# GTM900-breakout.net
KiCad netlist of a schematic drawn in EAGLE
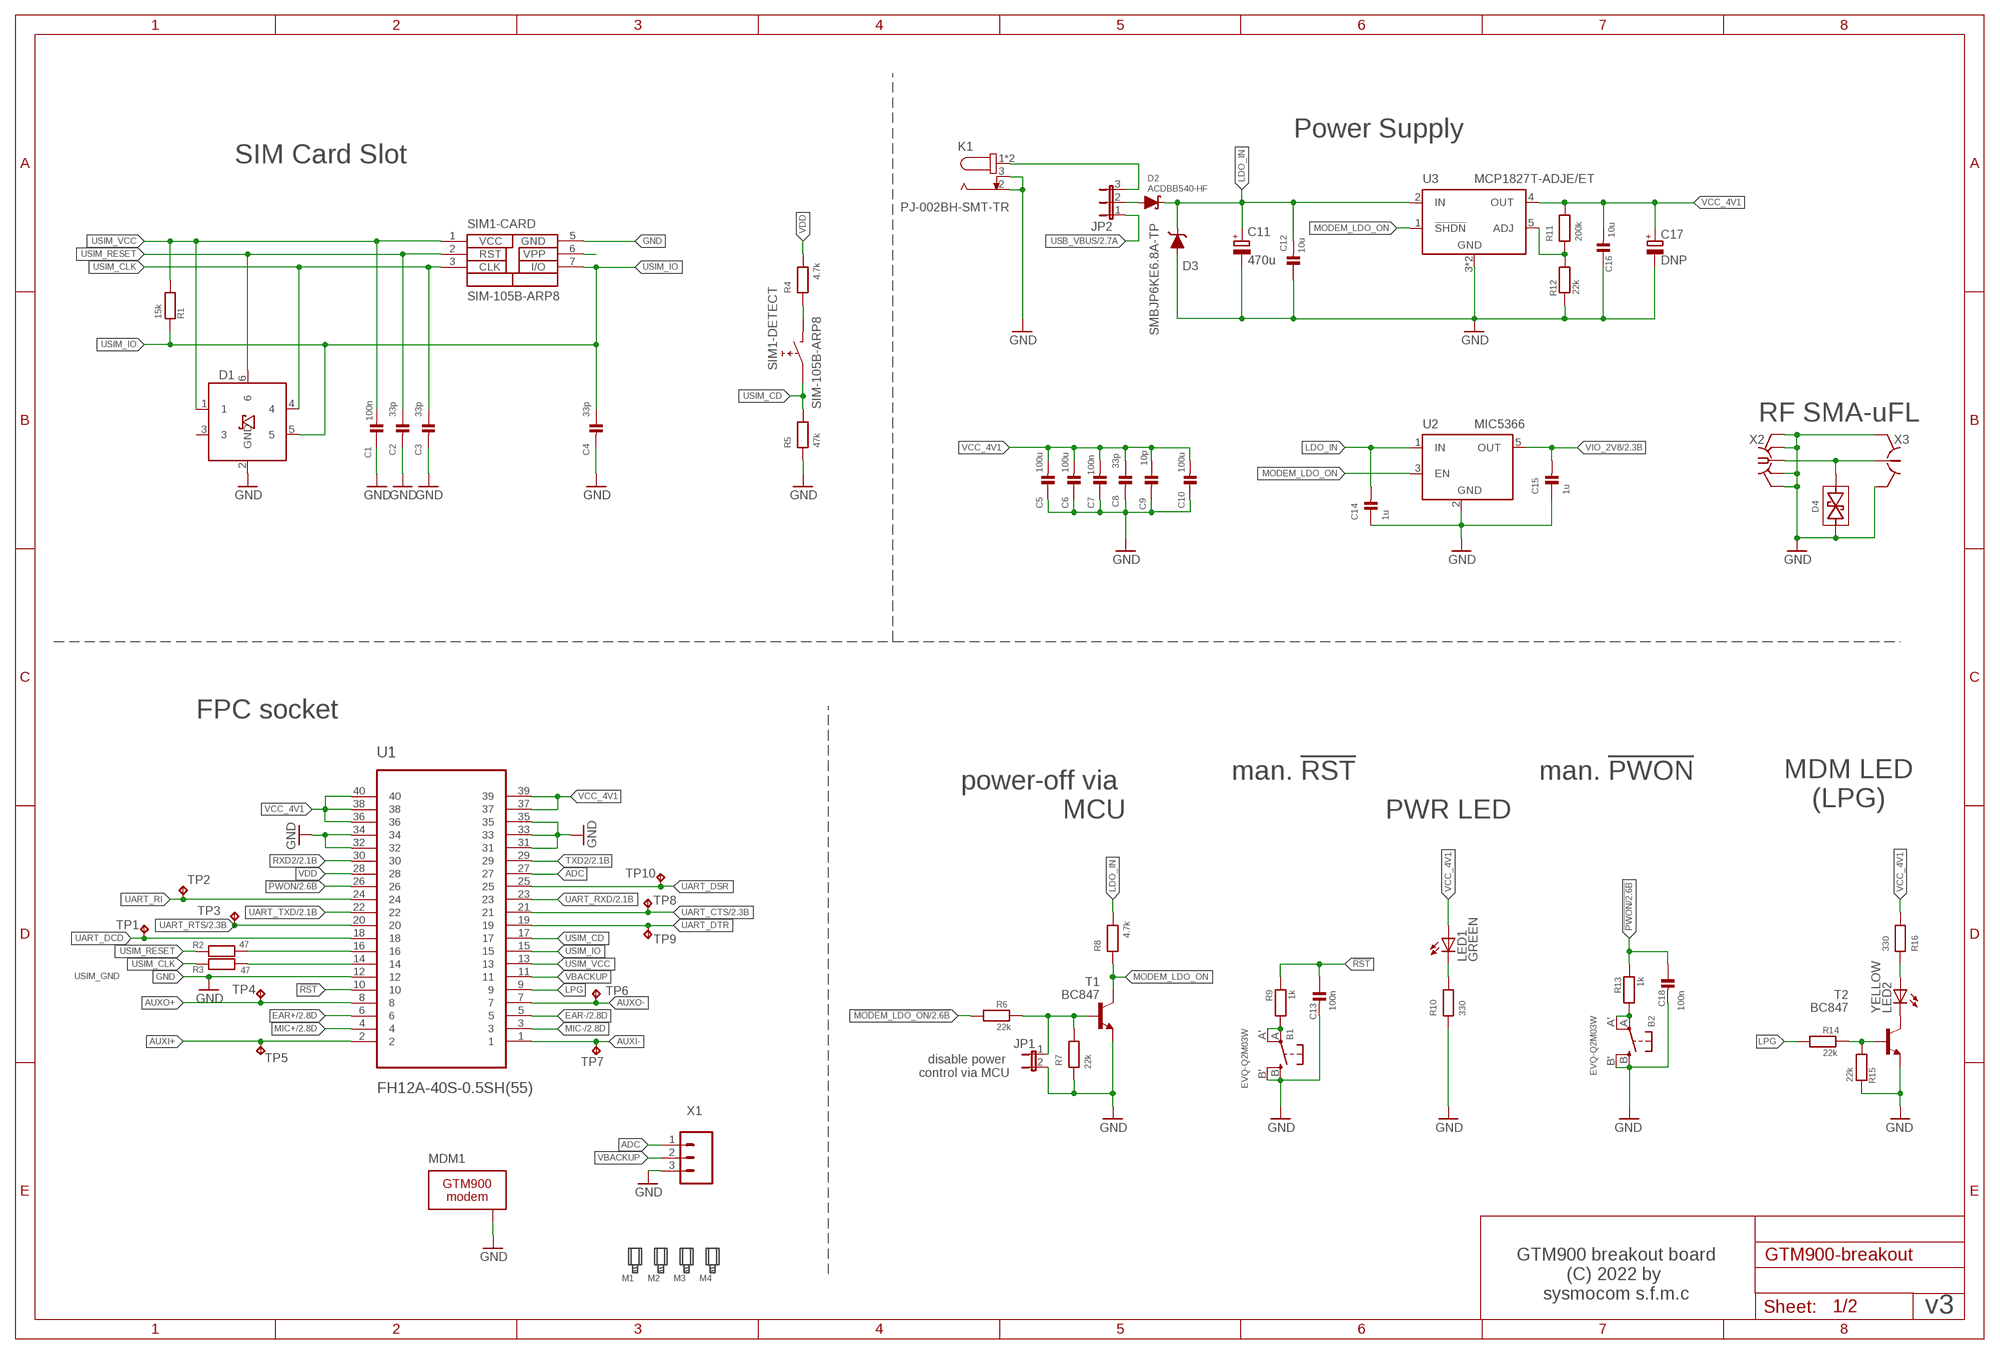
[diagram p0: schematic, sheet 1]
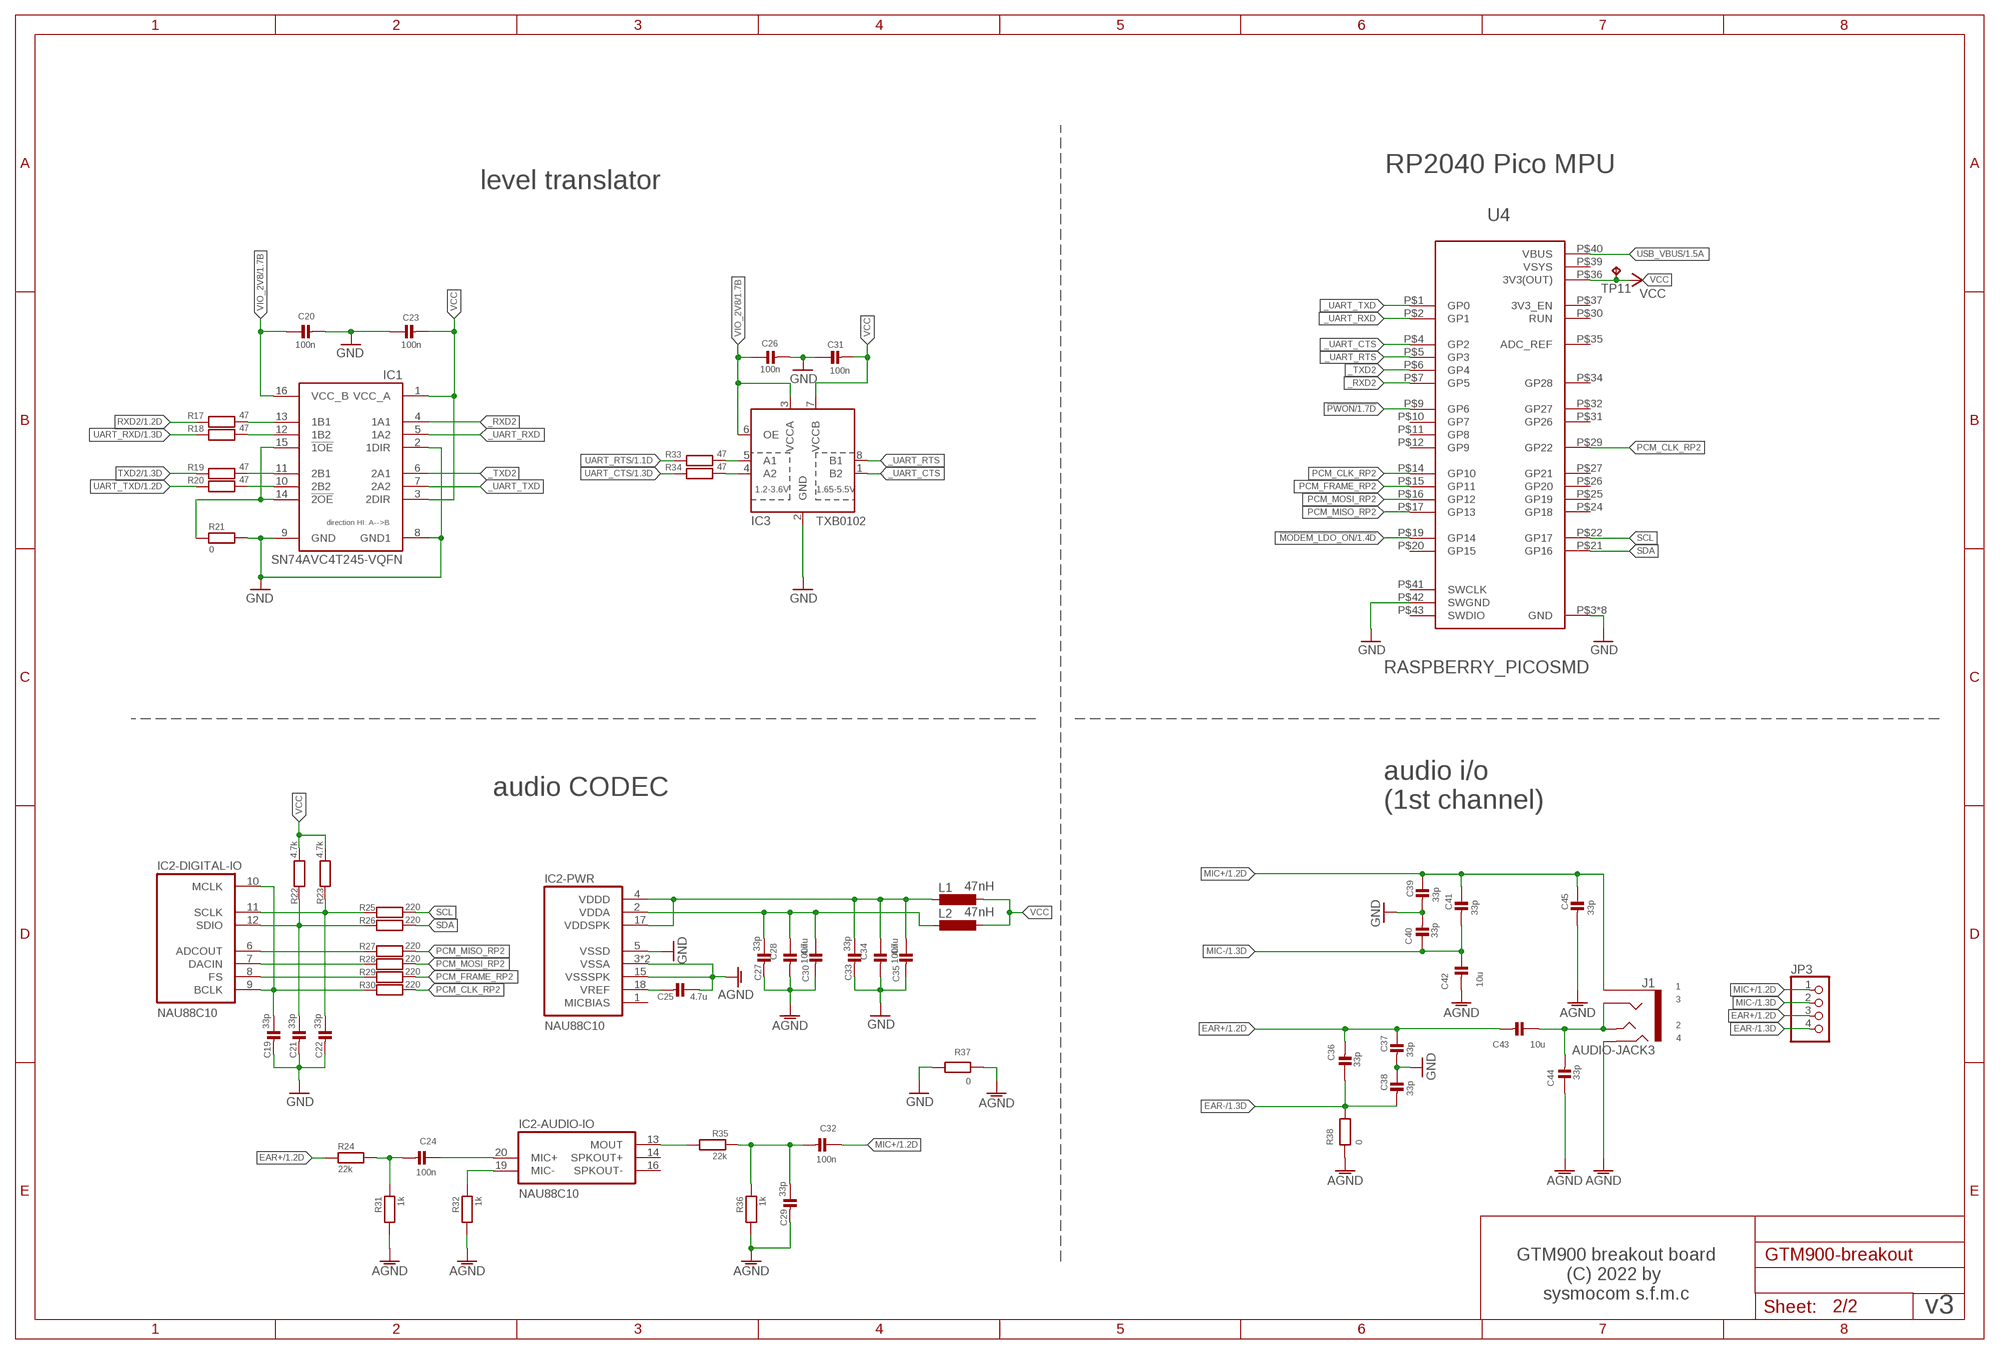
[diagram p1: schematic, sheet 2]

(export (version "E")
  (design (tool "Eeschema 10.0.6"))
  (components
    (comp (ref "C19")
      (value "33p")
      (footprint "eagle-import:_0402")
      (description "CAP CER 33PF 50V C0G/NP0 0402")
      (fields (field (name "LCSC_PART") "C70465") (field (name "MANUFACTURER") "Samsung Electro-Mechanics"))
      (libsource (lib "eagle-import") (part "CAP_CERAMIC_0402"))
    )
    (comp (ref "C20")
      (value "100n")
      (footprint "eagle-import:_0603")
      (description "CAP CER 0.1UF 50V X7R 0603")
      (fields (field (name "LCSC_PART") "C14663") (field (name "MANUFACTURER") "Samsung Electro-Mechanics"))
      (libsource (lib "eagle-import") (part "CAP_CERAMIC_0603"))
    )
    (comp (ref "C21")
      (value "33p")
      (footprint "eagle-import:_0402")
      (description "CAP CER 33PF 50V C0G/NP0 0402")
      (fields (field (name "LCSC_PART") "C70465") (field (name "MANUFACTURER") "Samsung Electro-Mechanics"))
      (libsource (lib "eagle-import") (part "CAP_CERAMIC_0402"))
    )
    (comp (ref "C22")
      (value "33p")
      (footprint "eagle-import:_0402")
      (description "CAP CER 33PF 50V C0G/NP0 0402")
      (fields (field (name "LCSC_PART") "C70465") (field (name "MANUFACTURER") "Samsung Electro-Mechanics"))
      (libsource (lib "eagle-import") (part "CAP_CERAMIC_0402"))
    )
    (comp (ref "C23")
      (value "100n")
      (footprint "eagle-import:_0603")
      (description "CAP CER 0.1UF 50V X7R 0603")
      (fields (field (name "LCSC_PART") "C14663") (field (name "MANUFACTURER") "Samsung Electro-Mechanics"))
      (libsource (lib "eagle-import") (part "CAP_CERAMIC_0603"))
    )
    (comp (ref "C24")
      (value "100n")
      (footprint "eagle-import:_0603")
      (description "CAP CER 0.1UF 50V X7R 0603")
      (fields (field (name "LCSC_PART") "C14663") (field (name "MANUFACTURER") "Samsung Electro-Mechanics"))
      (libsource (lib "eagle-import") (part "CAP_CERAMIC_0603"))
    )
    (comp (ref "C25")
      (value "4.7u")
      (footprint "eagle-import:_0603")
      (description "CAP CER 4.7UF 10V X5R 0603")
      (fields (field (name "LCSC_PART") "C109456") (field (name "MANUFACTURER") "Yageo"))
      (libsource (lib "eagle-import") (part "CAP_CERAMIC_0603"))
    )
    (comp (ref "C26")
      (value "100n")
      (footprint "eagle-import:_0603")
      (description "CAP CER 0.1UF 50V X7R 0603")
      (fields (field (name "LCSC_PART") "C14663") (field (name "MANUFACTURER") "Samsung Electro-Mechanics"))
      (libsource (lib "eagle-import") (part "CAP_CERAMIC_0603"))
    )
    (comp (ref "C27")
      (value "33p")
      (footprint "eagle-import:_0402")
      (description "CAP CER 33PF 50V C0G/NP0 0402")
      (fields (field (name "LCSC_PART") "C70465") (field (name "MANUFACTURER") "Samsung Electro-Mechanics"))
      (libsource (lib "eagle-import") (part "CAP_CERAMIC_0402"))
    )
    (comp (ref "C28")
      (value "100n")
      (footprint "eagle-import:_0603")
      (description "CAP CER 0.1UF 50V X7R 0603")
      (fields (field (name "LCSC_PART") "C14663") (field (name "MANUFACTURER") "Samsung Electro-Mechanics"))
      (libsource (lib "eagle-import") (part "CAP_CERAMIC_0603"))
    )
    (comp (ref "C29")
      (value "33p")
      (footprint "eagle-import:_0402")
      (description "CAP CER 33PF 50V C0G/NP0 0402")
      (fields (field (name "LCSC_PART") "C70465") (field (name "MANUFACTURER") "Samsung Electro-Mechanics"))
      (libsource (lib "eagle-import") (part "CAP_CERAMIC_0402"))
    )
    (comp (ref "C30")
      (value "4.7u")
      (footprint "eagle-import:_0603")
      (description "CAP CER 4.7UF 10V X5R 0603")
      (fields (field (name "LCSC_PART") "C109456") (field (name "MANUFACTURER") "Yageo"))
      (libsource (lib "eagle-import") (part "CAP_CERAMIC_0603"))
    )
    (comp (ref "C31")
      (value "100n")
      (footprint "eagle-import:_0603")
      (description "CAP CER 0.1UF 50V X7R 0603")
      (fields (field (name "LCSC_PART") "C14663") (field (name "MANUFACTURER") "Samsung Electro-Mechanics"))
      (libsource (lib "eagle-import") (part "CAP_CERAMIC_0603"))
    )
    (comp (ref "C32")
      (value "100n")
      (footprint "eagle-import:_0603")
      (description "CAP CER 0.1UF 50V X7R 0603")
      (fields (field (name "LCSC_PART") "C14663") (field (name "MANUFACTURER") "Samsung Electro-Mechanics"))
      (libsource (lib "eagle-import") (part "CAP_CERAMIC_0603"))
    )
    (comp (ref "C33")
      (value "33p")
      (footprint "eagle-import:_0402")
      (description "CAP CER 33PF 50V C0G/NP0 0402")
      (fields (field (name "LCSC_PART") "C70465") (field (name "MANUFACTURER") "Samsung Electro-Mechanics"))
      (libsource (lib "eagle-import") (part "CAP_CERAMIC_0402"))
    )
    (comp (ref "C34")
      (value "100n")
      (footprint "eagle-import:_0603")
      (description "CAP CER 0.1UF 50V X7R 0603")
      (fields (field (name "LCSC_PART") "C14663") (field (name "MANUFACTURER") "Samsung Electro-Mechanics"))
      (libsource (lib "eagle-import") (part "CAP_CERAMIC_0603"))
    )
    (comp (ref "C35")
      (value "4.7u")
      (footprint "eagle-import:_0603")
      (description "CAP CER 4.7UF 10V X5R 0603")
      (fields (field (name "LCSC_PART") "C109456") (field (name "MANUFACTURER") "Yageo"))
      (libsource (lib "eagle-import") (part "CAP_CERAMIC_0603"))
    )
    (comp (ref "C36")
      (value "33p")
      (footprint "eagle-import:_0402")
      (description "CAP CER 33PF 50V C0G/NP0 0402")
      (fields (field (name "LCSC_PART") "C70465") (field (name "MANUFACTURER") "Samsung Electro-Mechanics"))
      (libsource (lib "eagle-import") (part "CAP_CERAMIC_0402"))
    )
    (comp (ref "C37")
      (value "33p")
      (footprint "eagle-import:_0402")
      (description "CAP CER 33PF 50V C0G/NP0 0402")
      (fields (field (name "LCSC_PART") "C70465") (field (name "MANUFACTURER") "Samsung Electro-Mechanics"))
      (libsource (lib "eagle-import") (part "CAP_CERAMIC_0402"))
    )
    (comp (ref "C38")
      (value "33p")
      (footprint "eagle-import:_0402")
      (description "CAP CER 33PF 50V C0G/NP0 0402")
      (fields (field (name "LCSC_PART") "C70465") (field (name "MANUFACTURER") "Samsung Electro-Mechanics"))
      (libsource (lib "eagle-import") (part "CAP_CERAMIC_0402"))
    )
    (comp (ref "C39")
      (value "33p")
      (footprint "eagle-import:_0402")
      (description "CAP CER 33PF 50V C0G/NP0 0402")
      (fields (field (name "LCSC_PART") "C70465") (field (name "MANUFACTURER") "Samsung Electro-Mechanics"))
      (libsource (lib "eagle-import") (part "CAP_CERAMIC_0402"))
    )
    (comp (ref "C40")
      (value "33p")
      (footprint "eagle-import:_0402")
      (description "CAP CER 33PF 50V C0G/NP0 0402")
      (fields (field (name "LCSC_PART") "C70465") (field (name "MANUFACTURER") "Samsung Electro-Mechanics"))
      (libsource (lib "eagle-import") (part "CAP_CERAMIC_0402"))
    )
    (comp (ref "C41")
      (value "33p")
      (footprint "eagle-import:_0402")
      (description "CAP CER 33PF 50V C0G/NP0 0402")
      (fields (field (name "LCSC_PART") "C70465") (field (name "MANUFACTURER") "Samsung Electro-Mechanics"))
      (libsource (lib "eagle-import") (part "CAP_CERAMIC_0402"))
    )
    (comp (ref "C42")
      (value "10u")
      (footprint "eagle-import:_0805")
      (description "CAP CER 10UF 16V X5R 0805")
      (fields (field (name "LCSC_PART") "C408141") (field (name "MANUFACTURER") "Murata Electronics"))
      (libsource (lib "eagle-import") (part "CAP_CERAMIC_0805"))
    )
    (comp (ref "C43")
      (value "10u")
      (footprint "eagle-import:_0805")
      (description "CAP CER 10UF 16V X5R 0805")
      (fields (field (name "LCSC_PART") "C408141") (field (name "MANUFACTURER") "Murata Electronics"))
      (libsource (lib "eagle-import") (part "CAP_CERAMIC_0805"))
    )
    (comp (ref "C44")
      (value "33p")
      (footprint "eagle-import:_0402")
      (description "CAP CER 33PF 50V C0G/NP0 0402")
      (fields (field (name "LCSC_PART") "C70465") (field (name "MANUFACTURER") "Samsung Electro-Mechanics"))
      (libsource (lib "eagle-import") (part "CAP_CERAMIC_0402"))
    )
    (comp (ref "C45")
      (value "33p")
      (footprint "eagle-import:_0402")
      (description "CAP CER 33PF 50V C0G/NP0 0402")
      (fields (field (name "LCSC_PART") "C70465") (field (name "MANUFACTURER") "Samsung Electro-Mechanics"))
      (libsource (lib "eagle-import") (part "CAP_CERAMIC_0402"))
    )
    (comp (ref "IC1")
      (value "SN74AVC4T245-VQFN")
      (footprint "eagle-import:VQFN-N16")
      (description "IC TRANSLATION TXRX 3.6V 16VQFN")
      (fields (field (name "LCSC_PART") "C2872438") (field (name "MANUFACTURER") "Texas Instruments"))
      (libsource (lib "eagle-import") (part "SN74AVC4T245-VQFN"))
    )
    (comp (ref "IC2")
      (value "NAU88C10")
      (footprint "eagle-import:QFN20")
      (description "MONO AUDIO CODEC W/ SPEAKER DRIV")
      (fields
        (field (name "CLASS") "IC")
        (field (name "LCSC_PART") "C914208")
        (field (name "LINK") "https://www.digikey.com/en/products/detail/nuvoton-technology-corporation/NAU88C10YG/13147649")
        (field (name "MANUFACTURER") "Nuvoton Technology Corporation")
        (field (name "MANUFACTURERPARTNUMBER") "NAU88C10YG")
        (field (name "POPULATED") "TRUE")
        (field (name "ROHSCERTIFICATE") "ROHS3 Compliant")
        (field (name "SOURCE") "DIGIKEY")
        (field (name "SOURCEPARTNUMBER") "816-NAU88C10YG-ND")
      )
      (libsource (lib "eagle-import") (part "NAU88C10"))
    )
    (comp (ref "IC3")
      (value "TXB0102")
      (footprint "eagle-import:VSSOP-8")
      (description "IC TRANSLTR BIDIRECTIONAL 8VSSOP")
      (fields (field (name "LCSC_PART") "C60709") (field (name "MANUFACTURER") "Texas Instruments"))
      (libsource (lib "eagle-import") (part "TXB0102"))
    )
    (comp (ref "J1")
      (value "AUDIO-JACK3")
      (footprint "eagle-import:AUDIO-JACK-TRRS-SMD")
      (description "AUDIO JACK, 3.5 MM, RT, 4 CONDUC")
      (fields (field (name "LCSC_PART") "C4991637") (field (name "MANUFACTURER") "CUI Devices"))
      (libsource (lib "eagle-import") (part "AUDIO-JACK3"))
    )
    (comp (ref "JP3")
      (value "HEADER-1X476MIL")
      (footprint "eagle-import:1X04_ROUND_76")
      (description "NO DESCRIPTION")
      (fields
        (field (name "LCSC_PART") "UNKNOWN LCSC_PART")
        (field (name "MANUFACTURER") "UNKNOWN MANUFACTURER")
      )
      (libsource (lib "eagle-import") (part "HEADER-1X476MIL"))
    )
    (comp (ref "L1")
      (value "47nH")
      (footprint "eagle-import:_0603")
      (description "FIXED IND 47NH 400MA 700MOHM SMD")
      (fields (field (name "LCSC_PART") "C6135425") (field (name "MANUFACTURER") "Pulse Electronics"))
      (libsource (lib "eagle-import") (part "INDUCTOR_0603"))
    )
    (comp (ref "L2")
      (value "47nH")
      (footprint "eagle-import:_0603")
      (description "FIXED IND 47NH 400MA 700MOHM SMD")
      (fields (field (name "LCSC_PART") "C6135425") (field (name "MANUFACTURER") "Pulse Electronics"))
      (libsource (lib "eagle-import") (part "INDUCTOR_0603"))
    )
    (comp (ref "R17")
      (value "47")
      (footprint "eagle-import:_0603")
      (description "RES SMD 47 OHM 5% 1/10W 0603")
      (fields (field (name "LCSC_PART") "C114623") (field (name "MANUFACTURER") "Yageo"))
      (libsource (lib "eagle-import") (part "RESISTOR_0603"))
    )
    (comp (ref "R18")
      (value "47")
      (footprint "eagle-import:_0603")
      (description "RES SMD 47 OHM 5% 1/10W 0603")
      (fields (field (name "LCSC_PART") "C114623") (field (name "MANUFACTURER") "Yageo"))
      (libsource (lib "eagle-import") (part "RESISTOR_0603"))
    )
    (comp (ref "R19")
      (value "47")
      (footprint "eagle-import:_0603")
      (description "RES SMD 47 OHM 5% 1/10W 0603")
      (fields (field (name "LCSC_PART") "C114623") (field (name "MANUFACTURER") "Yageo"))
      (libsource (lib "eagle-import") (part "RESISTOR_0603"))
    )
    (comp (ref "R20")
      (value "47")
      (footprint "eagle-import:_0603")
      (description "RES SMD 47 OHM 5% 1/10W 0603")
      (fields (field (name "LCSC_PART") "C114623") (field (name "MANUFACTURER") "Yageo"))
      (libsource (lib "eagle-import") (part "RESISTOR_0603"))
    )
    (comp (ref "R21")
      (value "0")
      (footprint "eagle-import:_0603")
      (description "NO DESCRIPTION")
      (fields (field (name "LCSC_PART") "C136582") (field (name "MANUFACTURER") "UNKNOWN MANUFACTURER"))
      (libsource (lib "eagle-import") (part "RESISTOR_0603"))
    )
    (comp (ref "R22")
      (value "4.7k")
      (footprint "eagle-import:_0603")
      (description "RES SMD 4.7K OHM 5% 1/10W 0603")
      (fields (field (name "LCSC_PART") "C105428") (field (name "MANUFACTURER") "Yageo"))
      (libsource (lib "eagle-import") (part "RESISTOR_0603"))
    )
    (comp (ref "R23")
      (value "4.7k")
      (footprint "eagle-import:_0603")
      (description "RES SMD 4.7K OHM 5% 1/10W 0603")
      (fields (field (name "LCSC_PART") "C105428") (field (name "MANUFACTURER") "Yageo"))
      (libsource (lib "eagle-import") (part "RESISTOR_0603"))
    )
    (comp (ref "R24")
      (value "22k")
      (footprint "eagle-import:_0603")
      (description "RES 22K OHM 1% 1/10W 0603")
      (fields (field (name "LCSC_PART") "C114065") (field (name "MANUFACTURER") "YAGEO"))
      (libsource (lib "eagle-import") (part "RESISTOR_0603"))
    )
    (comp (ref "R25")
      (value "220")
      (footprint "eagle-import:_0603")
      (description "RES SMD 220 OHM 1% 1/10W 0603")
      (fields (field (name "LCSC_PART") "C107696") (field (name "MANUFACTURER") "Yageo"))
      (libsource (lib "eagle-import") (part "RESISTOR_0603"))
    )
    (comp (ref "R26")
      (value "220")
      (footprint "eagle-import:_0603")
      (description "RES SMD 220 OHM 1% 1/10W 0603")
      (fields (field (name "LCSC_PART") "C107696") (field (name "MANUFACTURER") "Yageo"))
      (libsource (lib "eagle-import") (part "RESISTOR_0603"))
    )
    (comp (ref "R27")
      (value "220")
      (footprint "eagle-import:_0603")
      (description "RES SMD 220 OHM 1% 1/10W 0603")
      (fields (field (name "LCSC_PART") "C107696") (field (name "MANUFACTURER") "Yageo"))
      (libsource (lib "eagle-import") (part "RESISTOR_0603"))
    )
    (comp (ref "R28")
      (value "220")
      (footprint "eagle-import:_0603")
      (description "RES SMD 220 OHM 1% 1/10W 0603")
      (fields (field (name "LCSC_PART") "C107696") (field (name "MANUFACTURER") "Yageo"))
      (libsource (lib "eagle-import") (part "RESISTOR_0603"))
    )
    (comp (ref "R29")
      (value "220")
      (footprint "eagle-import:_0603")
      (description "RES SMD 220 OHM 1% 1/10W 0603")
      (fields (field (name "LCSC_PART") "C107696") (field (name "MANUFACTURER") "Yageo"))
      (libsource (lib "eagle-import") (part "RESISTOR_0603"))
    )
    (comp (ref "R30")
      (value "220")
      (footprint "eagle-import:_0603")
      (description "RES SMD 220 OHM 1% 1/10W 0603")
      (fields (field (name "LCSC_PART") "C107696") (field (name "MANUFACTURER") "Yageo"))
      (libsource (lib "eagle-import") (part "RESISTOR_0603"))
    )
    (comp (ref "R31")
      (value "1k")
      (footprint "eagle-import:_0603")
      (description "RES SMD 1K OHM 0.5% 1/16W 0603")
      (fields (field (name "LCSC_PART") "C116692") (field (name "MANUFACTURER") "Susumu"))
      (libsource (lib "eagle-import") (part "RESISTOR_0603"))
    )
    (comp (ref "R32")
      (value "1k")
      (footprint "eagle-import:_0603")
      (description "RES SMD 1K OHM 0.5% 1/16W 0603")
      (fields (field (name "LCSC_PART") "C116692") (field (name "MANUFACTURER") "Susumu"))
      (libsource (lib "eagle-import") (part "RESISTOR_0603"))
    )
    (comp (ref "R33")
      (value "47")
      (footprint "eagle-import:_0603")
      (description "RES SMD 47 OHM 5% 1/10W 0603")
      (fields (field (name "LCSC_PART") "C114623") (field (name "MANUFACTURER") "Yageo"))
      (libsource (lib "eagle-import") (part "RESISTOR_0603"))
    )
    (comp (ref "R34")
      (value "47")
      (footprint "eagle-import:_0603")
      (description "RES SMD 47 OHM 5% 1/10W 0603")
      (fields (field (name "LCSC_PART") "C114623") (field (name "MANUFACTURER") "Yageo"))
      (libsource (lib "eagle-import") (part "RESISTOR_0603"))
    )
    (comp (ref "R35")
      (value "22k")
      (footprint "eagle-import:_0603")
      (description "RES 22K OHM 1% 1/10W 0603")
      (fields (field (name "LCSC_PART") "C114065") (field (name "MANUFACTURER") "YAGEO"))
      (libsource (lib "eagle-import") (part "RESISTOR_0603"))
    )
    (comp (ref "R36")
      (value "1k")
      (footprint "eagle-import:_0603")
      (description "RES SMD 1K OHM 0.5% 1/16W 0603")
      (fields (field (name "LCSC_PART") "C116692") (field (name "MANUFACTURER") "Susumu"))
      (libsource (lib "eagle-import") (part "RESISTOR_0603"))
    )
    (comp (ref "R37")
      (value "0")
      (footprint "eagle-import:_0603")
      (description "NO DESCRIPTION")
      (fields (field (name "LCSC_PART") "C136582") (field (name "MANUFACTURER") "UNKNOWN MANUFACTURER"))
      (libsource (lib "eagle-import") (part "RESISTOR_0603"))
    )
    (comp (ref "R38")
      (value "0")
      (footprint "eagle-import:_0603")
      (description "NO DESCRIPTION")
      (fields (field (name "LCSC_PART") "C136582") (field (name "MANUFACTURER") "UNKNOWN MANUFACTURER"))
      (libsource (lib "eagle-import") (part "RESISTOR_0603"))
    )
    (comp (ref "TP11")
      (value "TPTP10R")
      (footprint "eagle-import:TP10R")
      (description "NO DESCRIPTION")
      (fields
        (field (name "LCSC_PART") "UNKNOWN LCSC_PART")
        (field (name "MANUFACTURER") "UNKNOWN MANUFACTURER")
      )
      (libsource (lib "eagle-import") (part "TPTP10R"))
    )
    (comp (ref "U4")
      (value "RASPBERRY_PICOSMD")
      (footprint "eagle-import:PICO-PKG-SMD")
      (description "RASPBERRY PI PICO RP2040")
      (fields (field (name "LCSC_PART") "UNKNOWN LCSC_PART") (field (name "MANUFACTURER") "Raspberry Pi"))
      (libsource (lib "eagle-import") (part "RASPBERRY_PICOSMD"))
    )
    (comp (ref "B1")
      (value "EVQ-Q2M03W")
      (footprint "eagle-import:EVQ-Q2")
      (description "SWITCH TACTILE SPST-NO 0.02A 15V")
      (fields
        (field (name "LCSC_PART") "C713484")
        (field (name "MANUFACTURER") "Panasonic Electronic Components")
      )
      (libsource (lib "eagle-import") (part "SWITCH_TACT_SMT"))
    )
    (comp (ref "B2")
      (value "EVQ-Q2M03W")
      (footprint "eagle-import:EVQ-Q2")
      (description "SWITCH TACTILE SPST-NO 0.02A 15V")
      (fields
        (field (name "LCSC_PART") "C713484")
        (field (name "MANUFACTURER") "Panasonic Electronic Components")
      )
      (libsource (lib "eagle-import") (part "SWITCH_TACT_SMT"))
    )
    (comp (ref "C1")
      (value "100n")
      (footprint "eagle-import:_0603")
      (description "CAP CER 0.1UF 50V X7R 0603")
      (fields (field (name "LCSC_PART") "C14663") (field (name "MANUFACTURER") "Samsung Electro-Mechanics"))
      (libsource (lib "eagle-import") (part "CAP_CERAMIC_0603"))
    )
    (comp (ref "C2")
      (value "33p")
      (footprint "eagle-import:_0402")
      (description "CAP CER 33PF 50V C0G/NP0 0402")
      (fields (field (name "LCSC_PART") "C70465") (field (name "MANUFACTURER") "Samsung Electro-Mechanics"))
      (libsource (lib "eagle-import") (part "CAP_CERAMIC_0402"))
    )
    (comp (ref "C3")
      (value "33p")
      (footprint "eagle-import:_0402")
      (description "CAP CER 33PF 50V C0G/NP0 0402")
      (fields (field (name "LCSC_PART") "C70465") (field (name "MANUFACTURER") "Samsung Electro-Mechanics"))
      (libsource (lib "eagle-import") (part "CAP_CERAMIC_0402"))
    )
    (comp (ref "C4")
      (value "33p")
      (footprint "eagle-import:_0402")
      (description "CAP CER 33PF 50V C0G/NP0 0402")
      (fields (field (name "LCSC_PART") "C70465") (field (name "MANUFACTURER") "Samsung Electro-Mechanics"))
      (libsource (lib "eagle-import") (part "CAP_CERAMIC_0402"))
    )
    (comp (ref "C5")
      (value "100u")
      (footprint "eagle-import:1206")
      (description "CAP CER 100UF 6.3V X5R 1206")
      (fields (field (name "LCSC_PART") "C15008") (field (name "MANUFACTURER") "Samsung Electro-Mechanics"))
      (libsource (lib "eagle-import") (part "CAP_CERAMIC1206"))
    )
    (comp (ref "C6")
      (value "100u")
      (footprint "eagle-import:1206")
      (description "CAP CER 100UF 6.3V X5R 1206")
      (fields (field (name "LCSC_PART") "C15008") (field (name "MANUFACTURER") "Samsung Electro-Mechanics"))
      (libsource (lib "eagle-import") (part "CAP_CERAMIC1206"))
    )
    (comp (ref "C7")
      (value "100n")
      (footprint "eagle-import:_0603")
      (description "CAP CER 0.1UF 50V X7R 0603")
      (fields (field (name "LCSC_PART") "C14663") (field (name "MANUFACTURER") "Samsung Electro-Mechanics"))
      (libsource (lib "eagle-import") (part "CAP_CERAMIC_0603"))
    )
    (comp (ref "C8")
      (value "33p")
      (footprint "eagle-import:_0402")
      (description "CAP CER 33PF 50V C0G/NP0 0402")
      (fields (field (name "LCSC_PART") "C70465") (field (name "MANUFACTURER") "Samsung Electro-Mechanics"))
      (libsource (lib "eagle-import") (part "CAP_CERAMIC_0402"))
    )
    (comp (ref "C9")
      (value "10p")
      (footprint "eagle-import:_0603")
      (description "CAP CER 10PF 50V C0G/NP0 0603")
      (fields (field (name "LCSC_PART") "C106245") (field (name "MANUFACTURER") "KEMET"))
      (libsource (lib "eagle-import") (part "CAP_CERAMIC_0603"))
    )
    (comp (ref "C10")
      (value "100u")
      (footprint "eagle-import:1206")
      (description "CAP CER 100UF 6.3V X5R 1206")
      (fields (field (name "LCSC_PART") "C15008") (field (name "MANUFACTURER") "Samsung Electro-Mechanics"))
      (libsource (lib "eagle-import") (part "CAP_CERAMIC1206"))
    )
    (comp (ref "C11")
      (value "470u")
      (footprint "eagle-import:UD-8X10_NICHICON")
      (description "CAP ALUM 470UF 20% 6.3V SMD")
      (fields (field (name "LCSC_PART") "C445244") (field (name "MANUFACTURER") "Nichicon"))
      (libsource (lib "eagle-import") (part "CPOL-EUUD-8X10"))
    )
    (comp (ref "C12")
      (value "10u")
      (footprint "eagle-import:_0805")
      (description "CAP CER 10UF 16V X5R 0805")
      (fields (field (name "LCSC_PART") "C408141") (field (name "MANUFACTURER") "Murata Electronics"))
      (libsource (lib "eagle-import") (part "CAP_CERAMIC_0805"))
    )
    (comp (ref "C13")
      (value "100n")
      (footprint "eagle-import:_0603")
      (description "CAP CER 0.1UF 50V X7R 0603")
      (fields (field (name "LCSC_PART") "C14663") (field (name "MANUFACTURER") "Samsung Electro-Mechanics"))
      (libsource (lib "eagle-import") (part "CAP_CERAMIC_0603"))
    )
    (comp (ref "C14")
      (value "1u")
      (footprint "eagle-import:_0603")
      (description "CAP CER 1UF 16V X5R 0603")
      (fields (field (name "LCSC_PART") "C1592") (field (name "MANUFACTURER") "Samsung Electro-Mechanics"))
      (libsource (lib "eagle-import") (part "CAP_CERAMIC_0603"))
    )
    (comp (ref "C15")
      (value "1u")
      (footprint "eagle-import:_0603")
      (description "CAP CER 1UF 16V X5R 0603")
      (fields (field (name "LCSC_PART") "C1592") (field (name "MANUFACTURER") "Samsung Electro-Mechanics"))
      (libsource (lib "eagle-import") (part "CAP_CERAMIC_0603"))
    )
    (comp (ref "C16")
      (value "10u")
      (footprint "eagle-import:_0805")
      (description "CAP CER 10UF 16V X5R 0805")
      (fields (field (name "LCSC_PART") "C408141") (field (name "MANUFACTURER") "Murata Electronics"))
      (libsource (lib "eagle-import") (part "CAP_CERAMIC_0805"))
    )
    (comp (ref "C17")
      (value "DNP")
      (footprint "eagle-import:SMC_E")
      (description "NO DESCRIPTION")
      (fields
        (field (name "LCSC_PART") "UNKNOWN LCSC_PART")
        (field (name "MANUFACTURER") "UNKNOWN MANUFACTURER")
      )
      (libsource (lib "eagle-import") (part "CPOL-EUSMCE"))
    )
    (comp (ref "C18")
      (value "100n")
      (footprint "eagle-import:_0603")
      (description "CAP CER 0.1UF 50V X7R 0603")
      (fields (field (name "LCSC_PART") "C14663") (field (name "MANUFACTURER") "Samsung Electro-Mechanics"))
      (libsource (lib "eagle-import") (part "CAP_CERAMIC_0603"))
    )
    (comp (ref "D1")
      (value "PESD5V0UBV")
      (footprint "eagle-import:SOT666")
      (description "TVS DIODE 5V SOT666")
      (fields (field (name "LCSC_PART") "C552582") (field (name "MANUFACTURER") "Nexperia USA Inc."))
      (libsource (lib "eagle-import") (part "PESD5V0UBV"))
    )
    (comp (ref "D2")
      (value "ACDBB540-HF")
      (footprint "eagle-import:SMBDIODE")
      (description "DIODE SCHOTTKY 40V 5A DO214AA")
      (fields (field (name "LCSC_PART") "C3019736") (field (name "MANUFACTURER") "Comchip Technology"))
      (libsource (lib "eagle-import") (part "DIODE-SCHOTTKY-SMB"))
    )
    (comp (ref "D3")
      (value "SMBJP6KE6.8A-TP")
      (footprint "eagle-import:SMBDIODE")
      (description "TVS DIODE 5.8V 10.5V DO214AA")
      (fields (field (name "LCSC_PART") "C725414") (field (name "MANUFACTURER") "Micro Commercial Co"))
      (libsource (lib "eagle-import") (part "DIODE-TVS-SMB"))
    )
    (comp (ref "D4")
      (value "GG040205170N2P")
      (footprint "eagle-import:_0402")
      (description "TVS DIODE 5VWM 15.5VC 0402")
      (fields (field (name "LCSC_PART") "C597648") (field (name "MANUFACTURER") "KYOCERA AVX"))
      (libsource (lib "eagle-import") (part "TVSDIODE-BIDI-0402"))
    )
    (comp (ref "JP1")
      (value "JP1E")
      (footprint "eagle-import:JP1")
      (description "NO DESCRIPTION")
      (fields
        (field (name "LCSC_PART") "UNKNOWN LCSC_PART")
        (field (name "MANUFACTURER") "UNKNOWN MANUFACTURER")
      )
      (libsource (lib "eagle-import") (part "JP1E"))
    )
    (comp (ref "JP2")
      (value "JP2E")
      (footprint "eagle-import:JP2")
      (description "NO DESCRIPTION")
      (fields
        (field (name "LCSC_PART") "UNKNOWN LCSC_PART")
        (field (name "MANUFACTURER") "UNKNOWN MANUFACTURER")
      )
      (libsource (lib "eagle-import") (part "JP2E"))
    )
    (comp (ref "K1")
      (value "PJ-002BH-SMT-TR")
      (footprint "eagle-import:694108106102")
      (description "CONN PWR JACK 2.5X5.5MM SOLDER")
      (fields (field (name "LCSC_PART") "C3094235") (field (name "MANUFACTURER") "CUI Devices"))
      (libsource (lib "eagle-import") (part "694108106102"))
    )
    (comp (ref "LED1")
      (value "GREEN")
      (footprint "eagle-import:CHIP-LED0603")
      (description "NO DESCRIPTION")
      (fields (field (name "LCSC_PART") "C5554150") (field (name "MANUFACTURER") "UNKNOWN MANUFACTURER"))
      (libsource (lib "eagle-import") (part "LEDCHIP-LED0603"))
    )
    (comp (ref "LED2")
      (value "YELLOW")
      (footprint "eagle-import:CHIP-LED0603")
      (description "NO DESCRIPTION")
      (fields (field (name "LCSC_PART") "C5355459") (field (name "MANUFACTURER") "UNKNOWN MANUFACTURER"))
      (libsource (lib "eagle-import") (part "LEDCHIP-LED0603"))
    )
    (comp (ref "MDM1")
      (value "GTM900-BM2-SPACER")
      (footprint "eagle-import:GTM900-WRTHSPACER")
      (description "NO DESCRIPTION")
      (fields
        (field (name "LCSC_PART") "UNKNOWN LCSC_PART")
        (field (name "MANUFACTURER") "UNKNOWN MANUFACTURER")
      )
      (libsource (lib "eagle-import") (part "GTM900-BM2-SPACER"))
    )
    (comp (ref "R1")
      (value "15k")
      (footprint "eagle-import:_0603")
      (description "RES SMD 15K OHM 1% 1/10W 0603")
      (fields (field (name "LCSC_PART") "C114661") (field (name "MANUFACTURER") "Yageo"))
      (libsource (lib "eagle-import") (part "RESISTOR_0603"))
    )
    (comp (ref "R2")
      (value "47")
      (footprint "eagle-import:_0603")
      (description "RES SMD 47 OHM 5% 1/10W 0603")
      (fields (field (name "LCSC_PART") "C114623") (field (name "MANUFACTURER") "Yageo"))
      (libsource (lib "eagle-import") (part "RESISTOR_0603"))
    )
    (comp (ref "R3")
      (value "47")
      (footprint "eagle-import:_0603")
      (description "RES SMD 47 OHM 5% 1/10W 0603")
      (fields (field (name "LCSC_PART") "C114623") (field (name "MANUFACTURER") "Yageo"))
      (libsource (lib "eagle-import") (part "RESISTOR_0603"))
    )
    (comp (ref "R4")
      (value "4.7k")
      (footprint "eagle-import:_0603")
      (description "RES SMD 4.7K OHM 5% 1/10W 0603")
      (fields (field (name "LCSC_PART") "C105428") (field (name "MANUFACTURER") "Yageo"))
      (libsource (lib "eagle-import") (part "RESISTOR_0603"))
    )
    (comp (ref "R5")
      (value "47k")
      (footprint "eagle-import:_0603")
      (description "RES SMD 47K OHM 1% 1/10W 0603")
      (fields (field (name "LCSC_PART") "C105579") (field (name "MANUFACTURER") "Yageo"))
      (libsource (lib "eagle-import") (part "RESISTOR_0603"))
    )
    (comp (ref "R6")
      (value "22k")
      (footprint "eagle-import:_0603")
      (description "RES 22K OHM 1% 1/10W 0603")
      (fields (field (name "LCSC_PART") "C114065") (field (name "MANUFACTURER") "YAGEO"))
      (libsource (lib "eagle-import") (part "RESISTOR_0603"))
    )
    (comp (ref "R7")
      (value "22k")
      (footprint "eagle-import:_0603")
      (description "RES 22K OHM 1% 1/10W 0603")
      (fields (field (name "LCSC_PART") "C114065") (field (name "MANUFACTURER") "YAGEO"))
      (libsource (lib "eagle-import") (part "RESISTOR_0603"))
    )
    (comp (ref "R8")
      (value "4.7k")
      (footprint "eagle-import:_0603")
      (description "RES SMD 4.7K OHM 5% 1/10W 0603")
      (fields (field (name "LCSC_PART") "C105428") (field (name "MANUFACTURER") "Yageo"))
      (libsource (lib "eagle-import") (part "RESISTOR_0603"))
    )
    (comp (ref "R9")
      (value "1k")
      (footprint "eagle-import:_0603")
      (description "RES SMD 1K OHM 0.5% 1/16W 0603")
      (fields (field (name "LCSC_PART") "C116692") (field (name "MANUFACTURER") "Susumu"))
      (libsource (lib "eagle-import") (part "RESISTOR_0603"))
    )
    (comp (ref "R10")
      (value "330")
      (footprint "eagle-import:_0603")
      (description "RES SMD 330 OHM 5% 1/10W 0603")
      (fields (field (name "LCSC_PART") "C105879") (field (name "MANUFACTURER") "Yageo"))
      (libsource (lib "eagle-import") (part "RESISTOR_0603"))
    )
    (comp (ref "R11")
      (value "200k")
      (footprint "eagle-import:_0603")
      (description "RES SMD 200K OHM 1% 1/16W 0603")
      (fields
        (field (name "LCSC_PART") "C105574")
        (field (name "MANUFACTURER") "TE Connectivity Passive Product")
      )
      (libsource (lib "eagle-import") (part "RESISTOR_0603"))
    )
    (comp (ref "R12")
      (value "22k")
      (footprint "eagle-import:_0603")
      (description "RES 22K OHM 1% 1/10W 0603")
      (fields (field (name "LCSC_PART") "C114065") (field (name "MANUFACTURER") "YAGEO"))
      (libsource (lib "eagle-import") (part "RESISTOR_0603"))
    )
    (comp (ref "R13")
      (value "1k")
      (footprint "eagle-import:_0603")
      (description "RES SMD 1K OHM 0.5% 1/16W 0603")
      (fields (field (name "LCSC_PART") "C116692") (field (name "MANUFACTURER") "Susumu"))
      (libsource (lib "eagle-import") (part "RESISTOR_0603"))
    )
    (comp (ref "R14")
      (value "22k")
      (footprint "eagle-import:_0603")
      (description "RES 22K OHM 1% 1/10W 0603")
      (fields (field (name "LCSC_PART") "C114065") (field (name "MANUFACTURER") "YAGEO"))
      (libsource (lib "eagle-import") (part "RESISTOR_0603"))
    )
    (comp (ref "R15")
      (value "22k")
      (footprint "eagle-import:_0603")
      (description "RES 22K OHM 1% 1/10W 0603")
      (fields (field (name "LCSC_PART") "C114065") (field (name "MANUFACTURER") "YAGEO"))
      (libsource (lib "eagle-import") (part "RESISTOR_0603"))
    )
    (comp (ref "R16")
      (value "330")
      (footprint "eagle-import:_0603")
      (description "RES SMD 330 OHM 5% 1/10W 0603")
      (fields (field (name "LCSC_PART") "C105879") (field (name "MANUFACTURER") "Yageo"))
      (libsource (lib "eagle-import") (part "RESISTOR_0603"))
    )
    (comp (ref "SIM1")
      (value "SIM-105B-ARP8")
      (footprint "eagle-import:SIM-105B-ARP8")
      (description "CONN SIM CARD HINGED TYPE R/A")
      (fields
        (field (name "LCSC_PART") "C920196")
        (field (name "MANUFACTURER") "JAE Electronics")
        (field (name "CLASS") "SIM HOLDER")
        (field (name "LINK") "https://www.digikey.com/product-detail/en/jae-electronics/SF7W008S1AR900/670-2985-1-ND/8024733")
        (field (name "MANUFACTURERPARTNUMBER") "SF7W008S1AR900")
        (field (name "POPULATED") "TRUE")
        (field (name "ROHSCERTIFICATE") "RoHS Compliant")
        (field (name "SOURCE") "DIGIKEY")
        (field (name "SOURCEPARTNUMBER") "670-2985-1-ND")
      )
      (libsource (lib "eagle-import") (part "SIM-105B-ARP8"))
    )
    (comp (ref "T1")
      (value "BC847")
      (footprint "eagle-import:SOT23-BEC")
      (description "TRANS NPN 45V 0.1A SOT23")
      (fields (field (name "LCSC_PART") "C8664") (field (name "MANUFACTURER") "Nexperia USA Inc."))
      (libsource (lib "eagle-import") (part "-NPN-SOT23-BECBC847C"))
    )
    (comp (ref "T2")
      (value "BC847")
      (footprint "eagle-import:SOT23-BEC")
      (description "TRANS NPN 45V 0.1A SOT23")
      (fields (field (name "LCSC_PART") "C8664") (field (name "MANUFACTURER") "Nexperia USA Inc."))
      (libsource (lib "eagle-import") (part "-NPN-SOT23-BECBC847C"))
    )
    (comp (ref "TP1")
      (value "TPTP10R")
      (footprint "eagle-import:TP10R")
      (description "NO DESCRIPTION")
      (fields
        (field (name "LCSC_PART") "UNKNOWN LCSC_PART")
        (field (name "MANUFACTURER") "UNKNOWN MANUFACTURER")
      )
      (libsource (lib "eagle-import") (part "TPTP10R"))
    )
    (comp (ref "TP2")
      (value "TPTP10R")
      (footprint "eagle-import:TP10R")
      (description "NO DESCRIPTION")
      (fields
        (field (name "LCSC_PART") "UNKNOWN LCSC_PART")
        (field (name "MANUFACTURER") "UNKNOWN MANUFACTURER")
      )
      (libsource (lib "eagle-import") (part "TPTP10R"))
    )
    (comp (ref "TP3")
      (value "TPTP10R")
      (footprint "eagle-import:TP10R")
      (description "NO DESCRIPTION")
      (fields
        (field (name "LCSC_PART") "UNKNOWN LCSC_PART")
        (field (name "MANUFACTURER") "UNKNOWN MANUFACTURER")
      )
      (libsource (lib "eagle-import") (part "TPTP10R"))
    )
    (comp (ref "TP4")
      (value "TPTP10R")
      (footprint "eagle-import:TP10R")
      (description "NO DESCRIPTION")
      (fields
        (field (name "LCSC_PART") "UNKNOWN LCSC_PART")
        (field (name "MANUFACTURER") "UNKNOWN MANUFACTURER")
      )
      (libsource (lib "eagle-import") (part "TPTP10R"))
    )
    (comp (ref "TP5")
      (value "TPTP10R")
      (footprint "eagle-import:TP10R")
      (description "NO DESCRIPTION")
      (fields
        (field (name "LCSC_PART") "UNKNOWN LCSC_PART")
        (field (name "MANUFACTURER") "UNKNOWN MANUFACTURER")
      )
      (libsource (lib "eagle-import") (part "TPTP10R"))
    )
    (comp (ref "TP6")
      (value "TPTP10R")
      (footprint "eagle-import:TP10R")
      (description "NO DESCRIPTION")
      (fields
        (field (name "LCSC_PART") "UNKNOWN LCSC_PART")
        (field (name "MANUFACTURER") "UNKNOWN MANUFACTURER")
      )
      (libsource (lib "eagle-import") (part "TPTP10R"))
    )
    (comp (ref "TP7")
      (value "TPTP10R")
      (footprint "eagle-import:TP10R")
      (description "NO DESCRIPTION")
      (fields
        (field (name "LCSC_PART") "UNKNOWN LCSC_PART")
        (field (name "MANUFACTURER") "UNKNOWN MANUFACTURER")
      )
      (libsource (lib "eagle-import") (part "TPTP10R"))
    )
    (comp (ref "TP8")
      (value "TPTP10R")
      (footprint "eagle-import:TP10R")
      (description "NO DESCRIPTION")
      (fields
        (field (name "LCSC_PART") "UNKNOWN LCSC_PART")
        (field (name "MANUFACTURER") "UNKNOWN MANUFACTURER")
      )
      (libsource (lib "eagle-import") (part "TPTP10R"))
    )
    (comp (ref "TP9")
      (value "TPTP10R")
      (footprint "eagle-import:TP10R")
      (description "NO DESCRIPTION")
      (fields
        (field (name "LCSC_PART") "UNKNOWN LCSC_PART")
        (field (name "MANUFACTURER") "UNKNOWN MANUFACTURER")
      )
      (libsource (lib "eagle-import") (part "TPTP10R"))
    )
    (comp (ref "TP10")
      (value "TPTP10R")
      (footprint "eagle-import:TP10R")
      (description "NO DESCRIPTION")
      (fields
        (field (name "LCSC_PART") "UNKNOWN LCSC_PART")
        (field (name "MANUFACTURER") "UNKNOWN MANUFACTURER")
      )
      (libsource (lib "eagle-import") (part "TPTP10R"))
    )
    (comp (ref "U1")
      (value "FH12A-40S-0.5SH(55)")
      (footprint "eagle-import:HIROSE_FH12A-40S-0.5SH(55)")
      (description "CONN FFC FPC TOP 40POS 0.5MM R/A")
      (fields (field (name "LCSC_PART") "C506795") (field (name "MANUFACTURER") "Hirose Electric Co Ltd"))
      (libsource (lib "eagle-import") (part "FH12A-40S-0.5SH(55)"))
    )
    (comp (ref "U2")
      (value "MIC5366")
      (footprint "eagle-import:SC70-5")
      (description "IC REG LINEAR 2.8V 150MA SC70-5")
      (fields (field (name "LCSC_PART") "C626107") (field (name "MANUFACTURER") "Microchip Technology"))
      (libsource (lib "eagle-import") (part "LDO_FIXED_EN-MIC5365-YC5"))
    )
    (comp (ref "U3")
      (value "MCP1827T-ADJE/ET")
      (footprint "eagle-import:TI_KTT_DPAK2")
      (description "IC REG LIN POS ADJ 1.5A 5DDPAK")
      (fields (field (name "LCSC_PART") "C152196") (field (name "MANUFACTURER") "Microchip Technology"))
      (libsource (lib "eagle-import") (part "LDO_SHD_ADJMCP1827T-ADJE/ET"))
    )
    (comp (ref "X1")
      (value "PINHD-1X3PTH")
      (footprint "eagle-import:1X03")
      (description "NO DESCRIPTION")
      (fields
        (field (name "LCSC_PART") "UNKNOWN LCSC_PART")
        (field (name "MANUFACTURER") "UNKNOWN MANUFACTURER")
      )
      (libsource (lib "eagle-import") (part "PINHD-1X3PTH"))
    )
    (comp (ref "X2")
      (value "SMA-F-S-TH")
      (footprint "eagle-import:SMA-F-S-TH")
      (description "CONN SMA JACK STR 50 OHM PCB")
      (fields
        (field (name "LCSC_PART") "UNKNOWN LCSC_PART")
        (field (name "MANUFACTURER") "TE Connectivity AMP Connectors")
      )
      (libsource (lib "eagle-import") (part "SMA-F-S-TH"))
    )
    (comp (ref "X3")
      (value "HRS_UFL")
      (footprint "eagle-import:HRS_UFL")
      (description "CONN U.FL RCPT STR 50 OHM SMD")
      (fields (field (name "LCSC_PART") "C434812") (field (name "MANUFACTURER") "Hirose Electric Co Ltd"))
      (libsource (lib "eagle-import") (part "HRS_UFL"))
    )
  )
  (nets
    (net (code "1") (name "ADC") (class "Default")
      (node (ref "U1") (pin "27") (pinfunction "27_27") (pintype "passive"))
      (node (ref "X1") (pin "1") (pinfunction "1_1") (pintype "passive"))
    )
    (net (code "2") (name "AGND") (class "Default")
      (node (ref "C25") (pin "1") (pinfunction "1_1") (pintype "passive"))
      (node (ref "C27") (pin "2") (pinfunction "2_2") (pintype "passive"))
      (node (ref "C28") (pin "2") (pinfunction "2_2") (pintype "passive"))
      (node (ref "C29") (pin "2") (pinfunction "2_2") (pintype "passive"))
      (node (ref "C30") (pin "2") (pinfunction "2_2") (pintype "passive"))
      (node (ref "C42") (pin "2") (pinfunction "2_2") (pintype "passive"))
      (node (ref "C44") (pin "1") (pinfunction "1_1") (pintype "passive"))
      (node (ref "C45") (pin "2") (pinfunction "2_2") (pintype "passive"))
      (node (ref "IC2") (pin "15") (pinfunction "VSSSPK_15") (pintype "power_in"))
      (node (ref "IC2") (pin "3") (pinfunction "VSSA_3") (pintype "power_in"))
      (node (ref "IC2") (pin "EXP") (pinfunction "VSSA_EXP") (pintype "power_in"))
      (node (ref "J1") (pin "4") (pinfunction "RING2_4") (pintype "bidirectional"))
      (node (ref "R31") (pin "2") (pinfunction "2_2") (pintype "passive"))
      (node (ref "R32") (pin "2") (pinfunction "2_2") (pintype "passive"))
      (node (ref "R36") (pin "2") (pinfunction "2_2") (pintype "passive"))
      (node (ref "R37") (pin "1") (pinfunction "1_1") (pintype "passive"))
      (node (ref "R38") (pin "1") (pinfunction "1_1") (pintype "passive"))
    )
    (net (code "3") (name "AUXI+") (class "Default")
      (node (ref "TP5") (pin "TP") (pinfunction "TP_TP") (pintype "input"))
      (node (ref "U1") (pin "2") (pinfunction "2_2") (pintype "passive"))
    )
    (net (code "4") (name "AUXI-") (class "Default")
      (node (ref "TP7") (pin "TP") (pinfunction "TP_TP") (pintype "input"))
      (node (ref "U1") (pin "1") (pinfunction "1_1") (pintype "passive"))
    )
    (net (code "5") (name "AUXO+") (class "Default")
      (node (ref "TP4") (pin "TP") (pinfunction "TP_TP") (pintype "input"))
      (node (ref "U1") (pin "8") (pinfunction "8_8") (pintype "passive"))
    )
    (net (code "6") (name "AUXO-") (class "Default")
      (node (ref "TP6") (pin "TP") (pinfunction "TP_TP") (pintype "input"))
      (node (ref "U1") (pin "7") (pinfunction "7_7") (pintype "passive"))
    )
    (net (code "7") (name "EAR+") (class "Default")
      (node (ref "C36") (pin "2") (pinfunction "2_2") (pintype "passive"))
      (node (ref "C37") (pin "1") (pinfunction "1_1") (pintype "passive"))
      (node (ref "C43") (pin "2") (pinfunction "2_2") (pintype "passive"))
      (node (ref "JP3") (pin "3") (pinfunction "3_3") (pintype "passive"))
      (node (ref "R24") (pin "1") (pinfunction "1_1") (pintype "passive"))
      (node (ref "U1") (pin "6") (pinfunction "6_6") (pintype "passive"))
    )
    (net (code "8") (name "EAR-") (class "Default")
      (node (ref "C36") (pin "1") (pinfunction "1_1") (pintype "passive"))
      (node (ref "C38") (pin "2") (pinfunction "2_2") (pintype "passive"))
      (node (ref "JP3") (pin "4") (pinfunction "4_4") (pintype "passive"))
      (node (ref "R38") (pin "2") (pinfunction "2_2") (pintype "passive"))
      (node (ref "U1") (pin "5") (pinfunction "5_5") (pintype "passive"))
    )
    (net (code "9") (name "GND") (class "Default")
      (node (ref "B1") (pin "B") (pinfunction "S_B") (pintype "passive"))
      (node (ref "B1") (pin "B'") (pinfunction "S1_B'") (pintype "passive"))
      (node (ref "B2") (pin "B") (pinfunction "S_B") (pintype "passive"))
      (node (ref "B2") (pin "B'") (pinfunction "S1_B'") (pintype "passive"))
      (node (ref "C1") (pin "1") (pinfunction "1_1") (pintype "passive"))
      (node (ref "C10") (pin "1") (pinfunction "1_1") (pintype "passive"))
      (node (ref "C11") (pin "-") (pinfunction "-_-") (pintype "passive"))
      (node (ref "C12") (pin "1") (pinfunction "1_1") (pintype "passive"))
      (node (ref "C13") (pin "2") (pinfunction "2_2") (pintype "passive"))
      (node (ref "C14") (pin "1") (pinfunction "1_1") (pintype "passive"))
      (node (ref "C15") (pin "1") (pinfunction "1_1") (pintype "passive"))
      (node (ref "C16") (pin "1") (pinfunction "1_1") (pintype "passive"))
      (node (ref "C17") (pin "-") (pinfunction "-_-") (pintype "passive"))
      (node (ref "C18") (pin "2") (pinfunction "2_2") (pintype "passive"))
      (node (ref "C19") (pin "2") (pinfunction "2_2") (pintype "passive"))
      (node (ref "C2") (pin "2") (pinfunction "2_2") (pintype "passive"))
      (node (ref "C20") (pin "2") (pinfunction "2_2") (pintype "passive"))
      (node (ref "C21") (pin "2") (pinfunction "2_2") (pintype "passive"))
      (node (ref "C22") (pin "2") (pinfunction "2_2") (pintype "passive"))
      (node (ref "C23") (pin "1") (pinfunction "1_1") (pintype "passive"))
      (node (ref "C26") (pin "2") (pinfunction "2_2") (pintype "passive"))
      (node (ref "C3") (pin "2") (pinfunction "2_2") (pintype "passive"))
      (node (ref "C31") (pin "1") (pinfunction "1_1") (pintype "passive"))
      (node (ref "C33") (pin "2") (pinfunction "2_2") (pintype "passive"))
      (node (ref "C34") (pin "2") (pinfunction "2_2") (pintype "passive"))
      (node (ref "C35") (pin "2") (pinfunction "2_2") (pintype "passive"))
      (node (ref "C37") (pin "2") (pinfunction "2_2") (pintype "passive"))
      (node (ref "C38") (pin "1") (pinfunction "1_1") (pintype "passive"))
      (node (ref "C39") (pin "2") (pinfunction "2_2") (pintype "passive"))
      (node (ref "C4") (pin "2") (pinfunction "2_2") (pintype "passive"))
      (node (ref "C40") (pin "2") (pinfunction "2_2") (pintype "passive"))
      (node (ref "C5") (pin "1") (pinfunction "1_1") (pintype "passive"))
      (node (ref "C6") (pin "1") (pinfunction "1_1") (pintype "passive"))
      (node (ref "C7") (pin "1") (pinfunction "1_1") (pintype "passive"))
      (node (ref "C8") (pin "2") (pinfunction "2_2") (pintype "passive"))
      (node (ref "C9") (pin "2") (pinfunction "2_2") (pintype "passive"))
      (node (ref "D1") (pin "2") (pinfunction "GND_2") (pintype "passive"))
      (node (ref "D3") (pin "A") (pinfunction "A_A") (pintype "passive"))
      (node (ref "D4") (pin "1") (pinfunction "P$1_1") (pintype "bidirectional"))
      (node (ref "IC1") (pin "2") (pinfunction "1DIR_2") (pintype "input"))
      (node (ref "IC1") (pin "8") (pinfunction "GND1_8") (pintype "passive"))
      (node (ref "IC1") (pin "9") (pinfunction "GND_9") (pintype "passive"))
      (node (ref "IC2") (pin "5") (pinfunction "VSSD_5") (pintype "power_in"))
      (node (ref "IC3") (pin "2") (pinfunction "GND_2") (pintype "power_in"))
      (node (ref "JP1") (pin "2") (pinfunction "2_2") (pintype "passive"))
      (node (ref "K1") (pin "2") (pinfunction "2_2") (pintype "passive"))
      (node (ref "K1") (pin "3") (pinfunction "3_3") (pintype "passive"))
      (node (ref "MDM1") (pin "1") (pinfunction "P$1_1") (pintype "power_in"))
      (node (ref "MDM1") (pin "2") (pinfunction "P$1_2") (pintype "power_in"))
      (node (ref "MDM1") (pin "3") (pinfunction "P$1_3") (pintype "power_in"))
      (node (ref "MDM1") (pin "4") (pinfunction "P$1_4") (pintype "power_in"))
      (node (ref "R10") (pin "1") (pinfunction "1_1") (pintype "passive"))
      (node (ref "R12") (pin "2") (pinfunction "2_2") (pintype "passive"))
      (node (ref "R15") (pin "2") (pinfunction "2_2") (pintype "passive"))
      (node (ref "R21") (pin "2") (pinfunction "2_2") (pintype "passive"))
      (node (ref "R37") (pin "2") (pinfunction "2_2") (pintype "passive"))
      (node (ref "R5") (pin "1") (pinfunction "1_1") (pintype "passive"))
      (node (ref "R7") (pin "2") (pinfunction "2_2") (pintype "passive"))
      (node (ref "SIM1") (pin "5") (pinfunction "GND_5") (pintype "power_in"))
      (node (ref "T1") (pin "E") (pinfunction "E_E") (pintype "passive"))
      (node (ref "T2") (pin "E") (pinfunction "E_E") (pintype "passive"))
      (node (ref "U1") (pin "12") (pinfunction "12_12") (pintype "passive"))
      (node (ref "U1") (pin "31") (pinfunction "31_31") (pintype "passive"))
      (node (ref "U1") (pin "32") (pinfunction "32_32") (pintype "passive"))
      (node (ref "U1") (pin "33") (pinfunction "33_33") (pintype "passive"))
      (node (ref "U1") (pin "34") (pinfunction "34_34") (pintype "passive"))
      (node (ref "U1") (pin "35") (pinfunction "35_35") (pintype "passive"))
      (node (ref "U2") (pin "2") (pinfunction "GND_2") (pintype "power_in"))
      (node (ref "U3") (pin "3") (pinfunction "GND_3") (pintype "power_in"))
      (node (ref "U3") (pin "PAD") (pinfunction "GND_PAD") (pintype "power_in"))
      (node (ref "U4") (pin "P$13") (pinfunction "GND_P$13") (pintype "power_in"))
      (node (ref "U4") (pin "P$18") (pinfunction "GND_P$18") (pintype "power_in"))
      (node (ref "U4") (pin "P$23") (pinfunction "GND_P$23") (pintype "power_in"))
      (node (ref "U4") (pin "P$28") (pinfunction "GND_P$28") (pintype "power_in"))
      (node (ref "U4") (pin "P$3") (pinfunction "GND_P$3") (pintype "power_in"))
      (node (ref "U4") (pin "P$33") (pinfunction "GND_P$33") (pintype "power_in"))
      (node (ref "U4") (pin "P$38") (pinfunction "GND_P$38") (pintype "power_in"))
      (node (ref "U4") (pin "P$42") (pinfunction "SWGND_P$42") (pintype "power_in"))
      (node (ref "U4") (pin "P$8") (pinfunction "GND_P$8") (pintype "power_in"))
      (node (ref "X1") (pin "3") (pinfunction "3_3") (pintype "passive"))
      (node (ref "X2") (pin "G1") (pinfunction "GND_G1") (pintype "power_in"))
      (node (ref "X2") (pin "G2") (pinfunction "GND_G2") (pintype "power_in"))
      (node (ref "X2") (pin "G3") (pinfunction "GND_G3") (pintype "power_in"))
      (node (ref "X2") (pin "G4") (pinfunction "GND_G4") (pintype "power_in"))
      (node (ref "X3") (pin "GND@1") (pinfunction "GND_GND@1") (pintype "power_in"))
      (node (ref "X3") (pin "GND@2") (pinfunction "GND_GND@2") (pintype "power_in"))
    )
    (net (code "10") (name "LDO_IN") (class "Default")
      (node (ref "C11") (pin "+") (pinfunction "+_+") (pintype "passive"))
      (node (ref "C12") (pin "2") (pinfunction "2_2") (pintype "passive"))
      (node (ref "C14") (pin "2") (pinfunction "2_2") (pintype "passive"))
      (node (ref "D2") (pin "C") (pinfunction "C_C") (pintype "passive"))
      (node (ref "D3") (pin "C") (pinfunction "C_C") (pintype "passive"))
      (node (ref "R8") (pin "2") (pinfunction "2_2") (pintype "passive"))
      (node (ref "U2") (pin "1") (pinfunction "IN_1") (pintype "input"))
      (node (ref "U3") (pin "2") (pinfunction "IN_2") (pintype "input"))
    )
    (net (code "11") (name "LPG") (class "Default")
      (node (ref "R14") (pin "1") (pinfunction "1_1") (pintype "passive"))
      (node (ref "U1") (pin "9") (pinfunction "9_9") (pintype "passive"))
    )
    (net (code "12") (name "MIC+") (class "Default")
      (node (ref "C32") (pin "1") (pinfunction "1_1") (pintype "passive"))
      (node (ref "C39") (pin "1") (pinfunction "1_1") (pintype "passive"))
      (node (ref "C41") (pin "1") (pinfunction "1_1") (pintype "passive"))
      (node (ref "C45") (pin "1") (pinfunction "1_1") (pintype "passive"))
      (node (ref "J1") (pin "1") (pinfunction "EARTH_1") (pintype "bidirectional"))
      (node (ref "JP3") (pin "1") (pinfunction "1_1") (pintype "passive"))
      (node (ref "U1") (pin "4") (pinfunction "4_4") (pintype "passive"))
    )
    (net (code "13") (name "MIC-") (class "Default")
      (node (ref "C40") (pin "1") (pinfunction "1_1") (pintype "passive"))
      (node (ref "C41") (pin "2") (pinfunction "2_2") (pintype "passive"))
      (node (ref "C42") (pin "1") (pinfunction "1_1") (pintype "passive"))
      (node (ref "JP3") (pin "2") (pinfunction "2_2") (pintype "passive"))
      (node (ref "U1") (pin "3") (pinfunction "3_3") (pintype "passive"))
    )
    (net (code "14") (name "MICBIAS") (class "Default")
      (node (ref "IC2") (pin "1") (pinfunction "MICBIAS_1") (pintype "power_in"))
    )
    (net (code "15") (name "MODEM_LDO_ON") (class "Default")
      (node (ref "R8") (pin "1") (pinfunction "1_1") (pintype "passive"))
      (node (ref "T1") (pin "C") (pinfunction "C_C") (pintype "passive"))
      (node (ref "U2") (pin "3") (pinfunction "EN_3") (pintype "input"))
      (node (ref "U3") (pin "1") (pinfunction "~{SHDN}_1") (pintype "input"))
    )
    (net (code "16") (name "Net-(B1-P)") (class "Default")
      (node (ref "B1") (pin "A") (pinfunction "P_A") (pintype "passive"))
      (node (ref "B1") (pin "A'") (pinfunction "P1_A'") (pintype "passive"))
      (node (ref "R9") (pin "2") (pinfunction "2_2") (pintype "passive"))
    )
    (net (code "17") (name "Net-(B2-P)") (class "Default")
      (node (ref "B2") (pin "A") (pinfunction "P_A") (pintype "passive"))
      (node (ref "B2") (pin "A'") (pinfunction "P1_A'") (pintype "passive"))
      (node (ref "R13") (pin "2") (pinfunction "2_2") (pintype "passive"))
    )
    (net (code "18") (name "Net-(C24-Pad2)") (class "Default")
      (node (ref "C24") (pin "2") (pinfunction "2_2") (pintype "passive"))
      (node (ref "R24") (pin "2") (pinfunction "2_2") (pintype "passive"))
      (node (ref "R31") (pin "1") (pinfunction "1_1") (pintype "passive"))
    )
    (net (code "19") (name "Net-(C29-Pad1)") (class "Default")
      (node (ref "C29") (pin "1") (pinfunction "1_1") (pintype "passive"))
      (node (ref "C32") (pin "2") (pinfunction "2_2") (pintype "passive"))
      (node (ref "R35") (pin "2") (pinfunction "2_2") (pintype "passive"))
      (node (ref "R36") (pin "1") (pinfunction "1_1") (pintype "passive"))
    )
    (net (code "20") (name "Net-(D2-PadA)") (class "Default")
      (node (ref "D2") (pin "A") (pinfunction "A_A") (pintype "passive"))
      (node (ref "JP2") (pin "2") (pinfunction "2_2") (pintype "passive"))
    )
    (net (code "21") (name "Net-(D4-P$2)") (class "Default")
      (node (ref "D4") (pin "2") (pinfunction "P$2_2") (pintype "bidirectional"))
      (node (ref "X2") (pin "C") (pinfunction "1_C") (pintype "passive"))
      (node (ref "X3") (pin "SIG") (pinfunction "1_SIG") (pintype "passive"))
    )
    (net (code "22") (name "Net-(IC1-1B1)") (class "Default")
      (node (ref "IC1") (pin "13") (pinfunction "1B1_13") (pintype "bidirectional"))
      (node (ref "R17") (pin "1") (pinfunction "1_1") (pintype "passive"))
    )
    (net (code "23") (name "Net-(IC1-1B2)") (class "Default")
      (node (ref "IC1") (pin "12") (pinfunction "1B2_12") (pintype "bidirectional"))
      (node (ref "R18") (pin "1") (pinfunction "1_1") (pintype "passive"))
    )
    (net (code "24") (name "Net-(IC1-2B1)") (class "Default")
      (node (ref "IC1") (pin "11") (pinfunction "2B1_11") (pintype "bidirectional"))
      (node (ref "R19") (pin "1") (pinfunction "1_1") (pintype "passive"))
    )
    (net (code "25") (name "Net-(IC1-2B2)") (class "Default")
      (node (ref "IC1") (pin "10") (pinfunction "2B2_10") (pintype "bidirectional"))
      (node (ref "R20") (pin "1") (pinfunction "1_1") (pintype "passive"))
    )
    (net (code "26") (name "Net-(IC1-~{1OE})") (class "Default")
      (node (ref "IC1") (pin "14") (pinfunction "~{2OE}_14") (pintype "input"))
      (node (ref "IC1") (pin "15") (pinfunction "~{1OE}_15") (pintype "input"))
      (node (ref "R21") (pin "1") (pinfunction "1_1") (pintype "passive"))
    )
    (net (code "27") (name "Net-(IC2A-MIC+)") (class "Default")
      (node (ref "C24") (pin "1") (pinfunction "1_1") (pintype "passive"))
      (node (ref "IC2") (pin "20") (pinfunction "MIC+_20") (pintype "input"))
    )
    (net (code "28") (name "Net-(IC2A-MIC-)") (class "Default")
      (node (ref "IC2") (pin "19") (pinfunction "MIC-_19") (pintype "input"))
      (node (ref "R32") (pin "1") (pinfunction "1_1") (pintype "passive"))
    )
    (net (code "29") (name "Net-(IC2A-MOUT)") (class "Default")
      (node (ref "IC2") (pin "13") (pinfunction "MOUT_13") (pintype "output"))
      (node (ref "R35") (pin "1") (pinfunction "1_1") (pintype "passive"))
    )
    (net (code "30") (name "Net-(IC2B-ADCOUT)") (class "Default")
      (node (ref "IC2") (pin "6") (pinfunction "ADCOUT_6") (pintype "output"))
      (node (ref "R27") (pin "1") (pinfunction "1_1") (pintype "passive"))
    )
    (net (code "31") (name "Net-(IC2B-BCLK)") (class "Default")
      (node (ref "C19") (pin "1") (pinfunction "1_1") (pintype "passive"))
      (node (ref "IC2") (pin "10") (pinfunction "MCLK_10") (pintype "bidirectional"))
      (node (ref "IC2") (pin "9") (pinfunction "BCLK_9") (pintype "bidirectional"))
      (node (ref "R30") (pin "1") (pinfunction "1_1") (pintype "passive"))
    )
    (net (code "32") (name "Net-(IC2B-DACIN)") (class "Default")
      (node (ref "IC2") (pin "7") (pinfunction "DACIN_7") (pintype "input"))
      (node (ref "R28") (pin "1") (pinfunction "1_1") (pintype "passive"))
    )
    (net (code "33") (name "Net-(IC2B-FS)") (class "Default")
      (node (ref "IC2") (pin "8") (pinfunction "FS_8") (pintype "bidirectional"))
      (node (ref "R29") (pin "1") (pinfunction "1_1") (pintype "passive"))
    )
    (net (code "34") (name "Net-(IC2B-SCLK)") (class "Default")
      (node (ref "C22") (pin "1") (pinfunction "1_1") (pintype "passive"))
      (node (ref "IC2") (pin "11") (pinfunction "SCLK_11") (pintype "open_collector"))
      (node (ref "R23") (pin "1") (pinfunction "1_1") (pintype "passive"))
      (node (ref "R25") (pin "1") (pinfunction "1_1") (pintype "passive"))
    )
    (net (code "35") (name "Net-(IC2B-SDIO)") (class "Default")
      (node (ref "C21") (pin "1") (pinfunction "1_1") (pintype "passive"))
      (node (ref "IC2") (pin "12") (pinfunction "SDIO_12") (pintype "open_collector"))
      (node (ref "R22") (pin "1") (pinfunction "1_1") (pintype "passive"))
      (node (ref "R26") (pin "1") (pinfunction "1_1") (pintype "passive"))
    )
    (net (code "36") (name "Net-(IC2C-VDDA)") (class "Default")
      (node (ref "C27") (pin "1") (pinfunction "1_1") (pintype "passive"))
      (node (ref "C28") (pin "1") (pinfunction "1_1") (pintype "passive"))
      (node (ref "C30") (pin "1") (pinfunction "1_1") (pintype "passive"))
      (node (ref "IC2") (pin "2") (pinfunction "VDDA_2") (pintype "power_in"))
      (node (ref "L2") (pin "2") (pinfunction "2_2") (pintype "passive"))
    )
    (net (code "37") (name "Net-(IC2C-VDDD)") (class "Default")
      (node (ref "C33") (pin "1") (pinfunction "1_1") (pintype "passive"))
      (node (ref "C34") (pin "1") (pinfunction "1_1") (pintype "passive"))
      (node (ref "C35") (pin "1") (pinfunction "1_1") (pintype "passive"))
      (node (ref "IC2") (pin "17") (pinfunction "VDDSPK_17") (pintype "power_in"))
      (node (ref "IC2") (pin "4") (pinfunction "VDDD_4") (pintype "power_in"))
      (node (ref "L1") (pin "2") (pinfunction "2_2") (pintype "passive"))
    )
    (net (code "38") (name "Net-(IC2C-VREF)") (class "Default")
      (node (ref "C25") (pin "2") (pinfunction "2_2") (pintype "passive"))
      (node (ref "IC2") (pin "18") (pinfunction "VREF_18") (pintype "power_in"))
    )
    (net (code "39") (name "Net-(IC3-A1)") (class "Default")
      (node (ref "IC3") (pin "5") (pinfunction "A1_5") (pintype "bidirectional"))
      (node (ref "R33") (pin "1") (pinfunction "1_1") (pintype "passive"))
    )
    (net (code "40") (name "Net-(IC3-A2)") (class "Default")
      (node (ref "IC3") (pin "4") (pinfunction "A2_4") (pintype "bidirectional"))
      (node (ref "R34") (pin "1") (pinfunction "1_1") (pintype "passive"))
    )
    (net (code "41") (name "Net-(J1-RING1)") (class "Default")
      (node (ref "C43") (pin "1") (pinfunction "1_1") (pintype "passive"))
      (node (ref "C44") (pin "2") (pinfunction "2_2") (pintype "passive"))
      (node (ref "J1") (pin "2") (pinfunction "TIP_2") (pintype "bidirectional"))
      (node (ref "J1") (pin "3") (pinfunction "RING1_3") (pintype "bidirectional"))
    )
    (net (code "42") (name "Net-(JP1-Pad1)") (class "Default")
      (node (ref "JP1") (pin "1") (pinfunction "1_1") (pintype "passive"))
      (node (ref "R6") (pin "2") (pinfunction "2_2") (pintype "passive"))
      (node (ref "R7") (pin "1") (pinfunction "1_1") (pintype "passive"))
      (node (ref "T1") (pin "B") (pinfunction "B_B") (pintype "passive"))
    )
    (net (code "43") (name "Net-(JP2-Pad3)") (class "Default")
      (node (ref "JP2") (pin "3") (pinfunction "3_3") (pintype "passive"))
      (node (ref "K1") (pin "1") (pinfunction "1_1") (pintype "passive"))
      (node (ref "K1") (pin "1-1") (pinfunction "1_1-1") (pintype "passive"))
    )
    (net (code "44") (name "Net-(LED1-PadC)") (class "Default")
      (node (ref "LED1") (pin "C") (pinfunction "C_C") (pintype "passive"))
      (node (ref "R10") (pin "2") (pinfunction "2_2") (pintype "passive"))
    )
    (net (code "45") (name "Net-(LED2-PadA)") (class "Default")
      (node (ref "LED2") (pin "A") (pinfunction "A_A") (pintype "passive"))
      (node (ref "R16") (pin "2") (pinfunction "2_2") (pintype "passive"))
    )
    (net (code "46") (name "Net-(LED2-PadC)") (class "Default")
      (node (ref "LED2") (pin "C") (pinfunction "C_C") (pintype "passive"))
      (node (ref "T2") (pin "C") (pinfunction "C_C") (pintype "passive"))
    )
    (net (code "47") (name "Net-(R2-Pad1)") (class "Default")
      (node (ref "R2") (pin "1") (pinfunction "1_1") (pintype "passive"))
      (node (ref "U1") (pin "16") (pinfunction "16_16") (pintype "passive"))
    )
    (net (code "48") (name "Net-(R3-Pad1)") (class "Default")
      (node (ref "R3") (pin "1") (pinfunction "1_1") (pintype "passive"))
      (node (ref "U1") (pin "14") (pinfunction "14_14") (pintype "passive"))
    )
    (net (code "49") (name "Net-(R14-Pad2)") (class "Default")
      (node (ref "R14") (pin "2") (pinfunction "2_2") (pintype "passive"))
      (node (ref "R15") (pin "1") (pinfunction "1_1") (pintype "passive"))
      (node (ref "T2") (pin "B") (pinfunction "B_B") (pintype "passive"))
    )
    (net (code "50") (name "Net-(SIM1B-1)") (class "Default")
      (node (ref "R4") (pin "1") (pinfunction "1_1") (pintype "passive"))
      (node (ref "SIM1") (pin "82") (pinfunction "1_82") (pintype "passive"))
    )
    (net (code "51") (name "Net-(U3-ADJ)") (class "Default")
      (node (ref "R11") (pin "1") (pinfunction "1_1") (pintype "passive"))
      (node (ref "R12") (pin "1") (pinfunction "1_1") (pintype "passive"))
      (node (ref "U3") (pin "5") (pinfunction "ADJ_5") (pintype "passive"))
    )
    (net (code "52") (name "PCM_CLK_RP2") (class "Default")
      (node (ref "R30") (pin "2") (pinfunction "2_2") (pintype "passive"))
      (node (ref "U4") (pin "P$14") (pinfunction "GP10_P$14") (pintype "bidirectional"))
      (node (ref "U4") (pin "P$29") (pinfunction "GP22_P$29") (pintype "bidirectional"))
    )
    (net (code "53") (name "PCM_FRAME_RP2") (class "Default")
      (node (ref "R29") (pin "2") (pinfunction "2_2") (pintype "passive"))
      (node (ref "U4") (pin "P$15") (pinfunction "GP11_P$15") (pintype "bidirectional"))
    )
    (net (code "54") (name "PCM_MISO_RP2") (class "Default")
      (node (ref "R27") (pin "2") (pinfunction "2_2") (pintype "passive"))
      (node (ref "U4") (pin "P$17") (pinfunction "GP13_P$17") (pintype "bidirectional"))
    )
    (net (code "55") (name "PCM_MOSI_RP2") (class "Default")
      (node (ref "R28") (pin "2") (pinfunction "2_2") (pintype "passive"))
      (node (ref "U4") (pin "P$16") (pinfunction "GP12_P$16") (pintype "bidirectional"))
    )
    (net (code "56") (name "RXD2") (class "Default")
      (node (ref "R17") (pin "2") (pinfunction "2_2") (pintype "passive"))
      (node (ref "U1") (pin "30") (pinfunction "30_30") (pintype "passive"))
    )
    (net (code "57") (name "SCL") (class "Default")
      (node (ref "R25") (pin "2") (pinfunction "2_2") (pintype "passive"))
      (node (ref "U4") (pin "P$22") (pinfunction "GP17_P$22") (pintype "bidirectional"))
    )
    (net (code "58") (name "SDA") (class "Default")
      (node (ref "R26") (pin "2") (pinfunction "2_2") (pintype "passive"))
      (node (ref "U4") (pin "P$21") (pinfunction "GP16_P$21") (pintype "bidirectional"))
    )
    (net (code "59") (name "TXD2") (class "Default")
      (node (ref "R19") (pin "2") (pinfunction "2_2") (pintype "passive"))
      (node (ref "U1") (pin "29") (pinfunction "29_29") (pintype "passive"))
    )
    (net (code "60") (name "UART_CTS") (class "Default")
      (node (ref "R34") (pin "2") (pinfunction "2_2") (pintype "passive"))
      (node (ref "TP8") (pin "TP") (pinfunction "TP_TP") (pintype "input"))
      (node (ref "U1") (pin "21") (pinfunction "21_21") (pintype "passive"))
    )
    (net (code "61") (name "UART_DCD") (class "Default")
      (node (ref "TP1") (pin "TP") (pinfunction "TP_TP") (pintype "input"))
      (node (ref "U1") (pin "18") (pinfunction "18_18") (pintype "passive"))
    )
    (net (code "62") (name "UART_DSR") (class "Default")
      (node (ref "TP10") (pin "TP") (pinfunction "TP_TP") (pintype "input"))
      (node (ref "U1") (pin "25") (pinfunction "25_25") (pintype "passive"))
    )
    (net (code "63") (name "UART_DTR") (class "Default")
      (node (ref "TP9") (pin "TP") (pinfunction "TP_TP") (pintype "input"))
      (node (ref "U1") (pin "19") (pinfunction "19_19") (pintype "passive"))
    )
    (net (code "64") (name "UART_RI") (class "Default")
      (node (ref "TP2") (pin "TP") (pinfunction "TP_TP") (pintype "input"))
      (node (ref "U1") (pin "24") (pinfunction "24_24") (pintype "passive"))
    )
    (net (code "65") (name "UART_RTS") (class "Default")
      (node (ref "R33") (pin "2") (pinfunction "2_2") (pintype "passive"))
      (node (ref "TP3") (pin "TP") (pinfunction "TP_TP") (pintype "input"))
      (node (ref "U1") (pin "20") (pinfunction "20_20") (pintype "passive"))
    )
    (net (code "66") (name "UART_RXD") (class "Default")
      (node (ref "R18") (pin "2") (pinfunction "2_2") (pintype "passive"))
      (node (ref "U1") (pin "23") (pinfunction "23_23") (pintype "passive"))
    )
    (net (code "67") (name "UART_TXD") (class "Default")
      (node (ref "R20") (pin "2") (pinfunction "2_2") (pintype "passive"))
      (node (ref "U1") (pin "22") (pinfunction "22_22") (pintype "passive"))
    )
    (net (code "68") (name "USB_VBUS") (class "Default")
      (node (ref "JP2") (pin "1") (pinfunction "1_1") (pintype "passive"))
      (node (ref "U4") (pin "P$40") (pinfunction "VBUS_P$40") (pintype "power_in"))
    )
    (net (code "69") (name "USIM_CD") (class "Default")
      (node (ref "R5") (pin "2") (pinfunction "2_2") (pintype "passive"))
      (node (ref "SIM1") (pin "81") (pinfunction "0_81") (pintype "passive"))
      (node (ref "U1") (pin "17") (pinfunction "17_17") (pintype "passive"))
    )
    (net (code "70") (name "USIM_CLK") (class "Default")
      (node (ref "C3") (pin "1") (pinfunction "1_1") (pintype "passive"))
      (node (ref "D1") (pin "4") (pinfunction "4_4") (pintype "passive"))
      (node (ref "R3") (pin "2") (pinfunction "2_2") (pintype "passive"))
      (node (ref "SIM1") (pin "3") (pinfunction "CLK_3") (pintype "input"))
    )
    (net (code "71") (name "USIM_IO") (class "Default")
      (node (ref "C4") (pin "1") (pinfunction "1_1") (pintype "passive"))
      (node (ref "D1") (pin "5") (pinfunction "5_5") (pintype "passive"))
      (node (ref "R1") (pin "1") (pinfunction "1_1") (pintype "passive"))
      (node (ref "SIM1") (pin "7") (pinfunction "I/O_7") (pintype "bidirectional"))
      (node (ref "U1") (pin "15") (pinfunction "15_15") (pintype "passive"))
    )
    (net (code "72") (name "USIM_RESET") (class "Default")
      (node (ref "C2") (pin "1") (pinfunction "1_1") (pintype "passive"))
      (node (ref "D1") (pin "6") (pinfunction "6_6") (pintype "passive"))
      (node (ref "R2") (pin "2") (pinfunction "2_2") (pintype "passive"))
      (node (ref "SIM1") (pin "2") (pinfunction "RST_2") (pintype "input"))
    )
    (net (code "73") (name "USIM_VCC") (class "Default")
      (node (ref "C1") (pin "2") (pinfunction "2_2") (pintype "passive"))
      (node (ref "D1") (pin "1") (pinfunction "1_1") (pintype "passive"))
      (node (ref "R1") (pin "2") (pinfunction "2_2") (pintype "passive"))
      (node (ref "SIM1") (pin "1") (pinfunction "VCC_1") (pintype "power_in"))
      (node (ref "U1") (pin "13") (pinfunction "13_13") (pintype "passive"))
    )
    (net (code "74") (name "VBACKUP") (class "Default")
      (node (ref "U1") (pin "11") (pinfunction "11_11") (pintype "passive"))
      (node (ref "X1") (pin "2") (pinfunction "2_2") (pintype "passive"))
    )
    (net (code "75") (name "VCC") (class "Default")
      (node (ref "C23") (pin "2") (pinfunction "2_2") (pintype "passive"))
      (node (ref "C31") (pin "2") (pinfunction "2_2") (pintype "passive"))
      (node (ref "IC1") (pin "1") (pinfunction "VCC_A_1") (pintype "bidirectional"))
      (node (ref "IC1") (pin "3") (pinfunction "2DIR_3") (pintype "input"))
      (node (ref "IC3") (pin "7") (pinfunction "VCCB_7") (pintype "power_in"))
      (node (ref "L1") (pin "1") (pinfunction "1_1") (pintype "passive"))
      (node (ref "L2") (pin "1") (pinfunction "1_1") (pintype "passive"))
      (node (ref "R22") (pin "2") (pinfunction "2_2") (pintype "passive"))
      (node (ref "R23") (pin "2") (pinfunction "2_2") (pintype "passive"))
      (node (ref "TP11") (pin "TP") (pinfunction "TP_TP") (pintype "input"))
      (node (ref "U4") (pin "P$36") (pinfunction "3V3(OUT)_P$36") (pintype "power_in"))
    )
    (net (code "76") (name "VCC_4V1") (class "Default")
      (node (ref "C10") (pin "2") (pinfunction "2_2") (pintype "passive"))
      (node (ref "C16") (pin "2") (pinfunction "2_2") (pintype "passive"))
      (node (ref "C17") (pin "+") (pinfunction "+_+") (pintype "passive"))
      (node (ref "C5") (pin "2") (pinfunction "2_2") (pintype "passive"))
      (node (ref "C6") (pin "2") (pinfunction "2_2") (pintype "passive"))
      (node (ref "C7") (pin "2") (pinfunction "2_2") (pintype "passive"))
      (node (ref "C8") (pin "1") (pinfunction "1_1") (pintype "passive"))
      (node (ref "C9") (pin "1") (pinfunction "1_1") (pintype "passive"))
      (node (ref "LED1") (pin "A") (pinfunction "A_A") (pintype "passive"))
      (node (ref "R11") (pin "2") (pinfunction "2_2") (pintype "passive"))
      (node (ref "R16") (pin "1") (pinfunction "1_1") (pintype "passive"))
      (node (ref "U1") (pin "36") (pinfunction "36_36") (pintype "passive"))
      (node (ref "U1") (pin "37") (pinfunction "37_37") (pintype "passive"))
      (node (ref "U1") (pin "38") (pinfunction "38_38") (pintype "passive"))
      (node (ref "U1") (pin "39") (pinfunction "39_39") (pintype "passive"))
      (node (ref "U1") (pin "40") (pinfunction "40_40") (pintype "passive"))
      (node (ref "U3") (pin "4") (pinfunction "OUT_4") (pintype "passive"))
    )
    (net (code "77") (name "VDD") (class "Default")
      (node (ref "R4") (pin "2") (pinfunction "2_2") (pintype "passive"))
      (node (ref "U1") (pin "28") (pinfunction "28_28") (pintype "passive"))
    )
    (net (code "78") (name "VIO_2V8") (class "Default")
      (node (ref "C15") (pin "2") (pinfunction "2_2") (pintype "passive"))
      (node (ref "C20") (pin "1") (pinfunction "1_1") (pintype "passive"))
      (node (ref "C26") (pin "1") (pinfunction "1_1") (pintype "passive"))
      (node (ref "IC1") (pin "16") (pinfunction "VCC_B_16") (pintype "power_in"))
      (node (ref "IC3") (pin "3") (pinfunction "VCCA_3") (pintype "power_in"))
      (node (ref "IC3") (pin "6") (pinfunction "OE_6") (pintype "input"))
      (node (ref "U2") (pin "5") (pinfunction "OUT_5") (pintype "passive"))
    )
    (net (code "79") (name "VSYS") (class "Default")
      (node (ref "U4") (pin "P$39") (pinfunction "VSYS_P$39") (pintype "power_in"))
    )
    (net (code "80") (name "_RXD2") (class "Default")
      (node (ref "IC1") (pin "4") (pinfunction "1A1_4") (pintype "bidirectional"))
      (node (ref "U4") (pin "P$7") (pinfunction "GP5_P$7") (pintype "bidirectional"))
    )
    (net (code "81") (name "_TXD2") (class "Default")
      (node (ref "IC1") (pin "6") (pinfunction "2A1_6") (pintype "bidirectional"))
      (node (ref "U4") (pin "P$6") (pinfunction "GP4_P$6") (pintype "bidirectional"))
    )
    (net (code "82") (name "_UART_CTS") (class "Default")
      (node (ref "IC3") (pin "1") (pinfunction "B2_1") (pintype "bidirectional"))
      (node (ref "U4") (pin "P$4") (pinfunction "GP2_P$4") (pintype "bidirectional"))
    )
    (net (code "83") (name "_UART_RTS") (class "Default")
      (node (ref "IC3") (pin "8") (pinfunction "B1_8") (pintype "bidirectional"))
      (node (ref "U4") (pin "P$5") (pinfunction "GP3_P$5") (pintype "bidirectional"))
    )
    (net (code "84") (name "_UART_RXD") (class "Default")
      (node (ref "IC1") (pin "5") (pinfunction "1A2_5") (pintype "bidirectional"))
      (node (ref "U4") (pin "P$2") (pinfunction "GP1_P$2") (pintype "bidirectional"))
    )
    (net (code "85") (name "_UART_TXD") (class "Default")
      (node (ref "IC1") (pin "7") (pinfunction "2A2_7") (pintype "bidirectional"))
      (node (ref "U4") (pin "P$1") (pinfunction "GP0_P$1") (pintype "bidirectional"))
    )
    (net (code "86") (name "unconnected-(D1-Pad3)") (class "Default")
      (node (ref "D1") (pin "3") (pinfunction "3_3") (pintype "passive"))
    )
    (net (code "87") (name "unconnected-(IC2A-SPKOUT+-Pad14)") (class "Default")
      (node (ref "IC2") (pin "14") (pinfunction "SPKOUT+_14") (pintype "output"))
    )
    (net (code "88") (name "unconnected-(IC2A-SPKOUT--Pad16)") (class "Default")
      (node (ref "IC2") (pin "16") (pinfunction "SPKOUT-_16") (pintype "output"))
    )
    (net (code "89") (name "unconnected-(SIM1A-VPP-Pad6)") (class "Default")
      (node (ref "SIM1") (pin "6") (pinfunction "VPP_6") (pintype "power_in"))
    )
    (net (code "90") (name "unconnected-(U4-3V3_EN-PadP$37)") (class "Default")
      (node (ref "U4") (pin "P$37") (pinfunction "3V3_EN_P$37") (pintype "input"))
    )
    (net (code "91") (name "unconnected-(U4-ADC_REF-PadP$35)") (class "Default")
      (node (ref "U4") (pin "P$35") (pinfunction "ADC_REF_P$35") (pintype "input"))
    )
    (net (code "92") (name "unconnected-(U4-GP7-PadP$10)") (class "Default")
      (node (ref "U4") (pin "P$10") (pinfunction "GP7_P$10") (pintype "bidirectional"))
    )
    (net (code "93") (name "unconnected-(U4-GP8-PadP$11)") (class "Default")
      (node (ref "U4") (pin "P$11") (pinfunction "GP8_P$11") (pintype "bidirectional"))
    )
    (net (code "94") (name "unconnected-(U4-GP9-PadP$12)") (class "Default")
      (node (ref "U4") (pin "P$12") (pinfunction "GP9_P$12") (pintype "bidirectional"))
    )
    (net (code "95") (name "unconnected-(U4-GP15-PadP$20)") (class "Default")
      (node (ref "U4") (pin "P$20") (pinfunction "GP15_P$20") (pintype "bidirectional"))
    )
    (net (code "96") (name "unconnected-(U4-GP18-PadP$24)") (class "Default")
      (node (ref "U4") (pin "P$24") (pinfunction "GP18_P$24") (pintype "bidirectional"))
    )
    (net (code "97") (name "unconnected-(U4-GP19-PadP$25)") (class "Default")
      (node (ref "U4") (pin "P$25") (pinfunction "GP19_P$25") (pintype "bidirectional"))
    )
    (net (code "98") (name "unconnected-(U4-GP20-PadP$26)") (class "Default")
      (node (ref "U4") (pin "P$26") (pinfunction "GP20_P$26") (pintype "bidirectional"))
    )
    (net (code "99") (name "unconnected-(U4-GP21-PadP$27)") (class "Default")
      (node (ref "U4") (pin "P$27") (pinfunction "GP21_P$27") (pintype "bidirectional"))
    )
    (net (code "100") (name "unconnected-(U4-GP26-PadP$31)") (class "Default")
      (node (ref "U4") (pin "P$31") (pinfunction "GP26_P$31") (pintype "bidirectional"))
    )
    (net (code "101") (name "unconnected-(U4-GP27-PadP$32)") (class "Default")
      (node (ref "U4") (pin "P$32") (pinfunction "GP27_P$32") (pintype "bidirectional"))
    )
    (net (code "102") (name "unconnected-(U4-GP28-PadP$34)") (class "Default")
      (node (ref "U4") (pin "P$34") (pinfunction "GP28_P$34") (pintype "bidirectional"))
    )
    (net (code "103") (name "unconnected-(U4-RUN-PadP$30)") (class "Default")
      (node (ref "U4") (pin "P$30") (pinfunction "RUN_P$30") (pintype "input"))
    )
    (net (code "104") (name "unconnected-(U4-SWCLK-PadP$41)") (class "Default")
      (node (ref "U4") (pin "P$41") (pinfunction "SWCLK_P$41") (pintype "input"))
    )
    (net (code "105") (name "unconnected-(U4-SWDIO-PadP$43)") (class "Default")
      (node (ref "U4") (pin "P$43") (pinfunction "SWDIO_P$43") (pintype "bidirectional"))
    )
    (net (code "106") (name "~{MODEM_LDO_ON}") (class "Default")
      (node (ref "R6") (pin "1") (pinfunction "1_1") (pintype "passive"))
      (node (ref "U4") (pin "P$19") (pinfunction "GP14_P$19") (pintype "bidirectional"))
    )
    (net (code "107") (name "~{PWON}") (class "Default")
      (node (ref "C18") (pin "1") (pinfunction "1_1") (pintype "passive"))
      (node (ref "R13") (pin "1") (pinfunction "1_1") (pintype "passive"))
      (node (ref "U1") (pin "26") (pinfunction "26_26") (pintype "passive"))
      (node (ref "U4") (pin "P$9") (pinfunction "GP6_P$9") (pintype "bidirectional"))
    )
    (net (code "108") (name "~{RST}") (class "Default")
      (node (ref "C13") (pin "1") (pinfunction "1_1") (pintype "passive"))
      (node (ref "R9") (pin "1") (pinfunction "1_1") (pintype "passive"))
      (node (ref "U1") (pin "10") (pinfunction "10_10") (pintype "passive"))
    )
  )
)
